# p8x-backplane-a.net
KiCad netlist of a schematic drawn in EAGLE
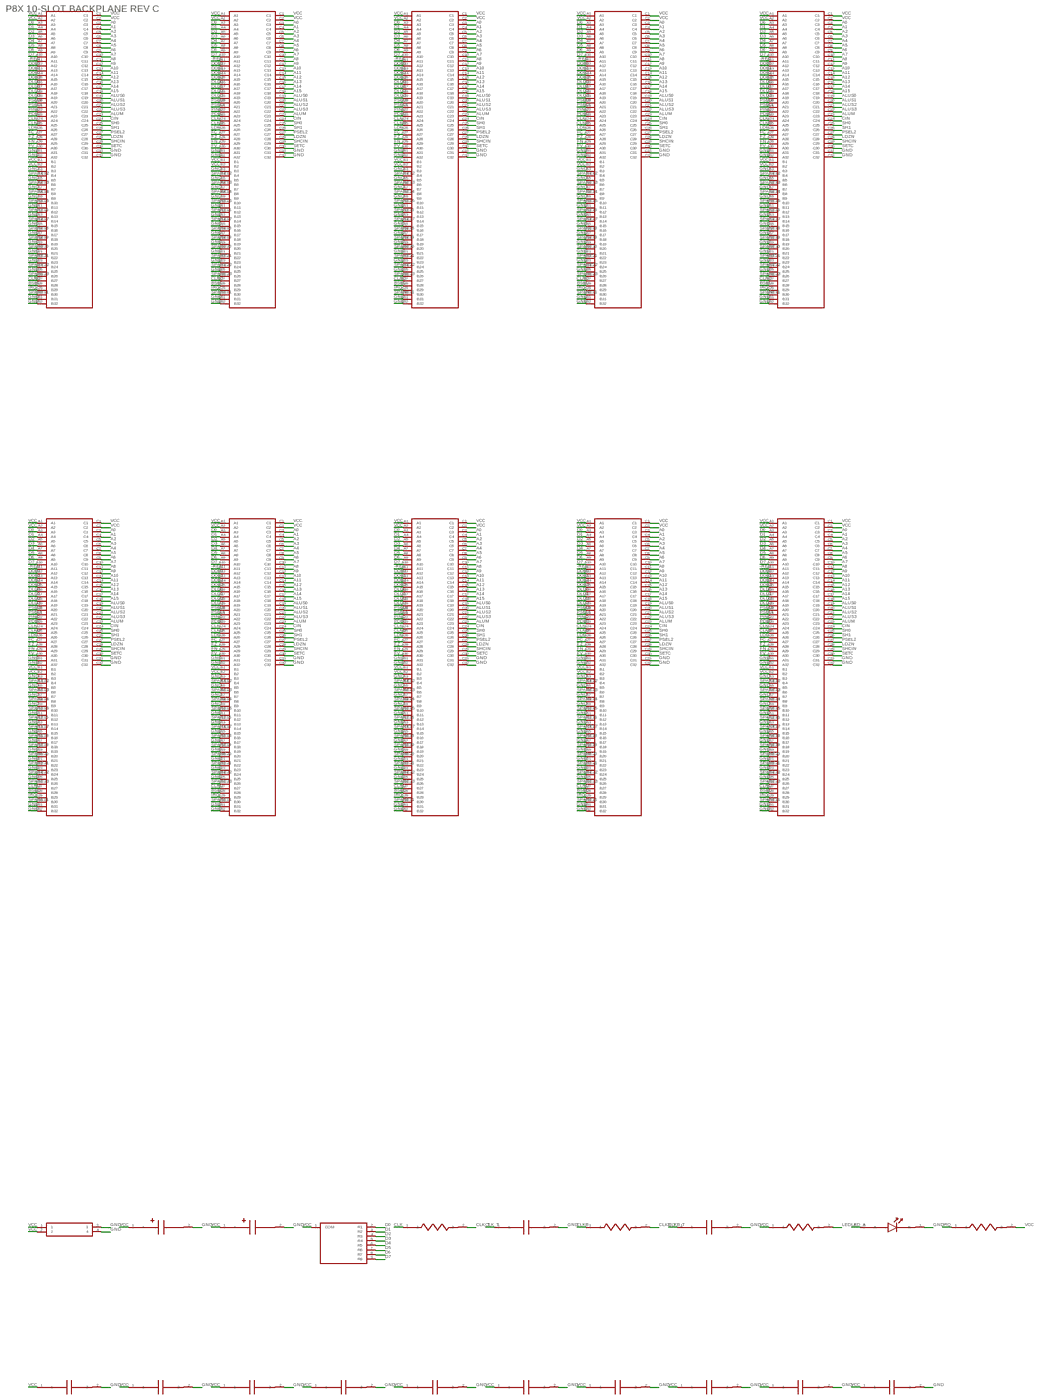
[diagram p0: schematic, sheet 1, overview]
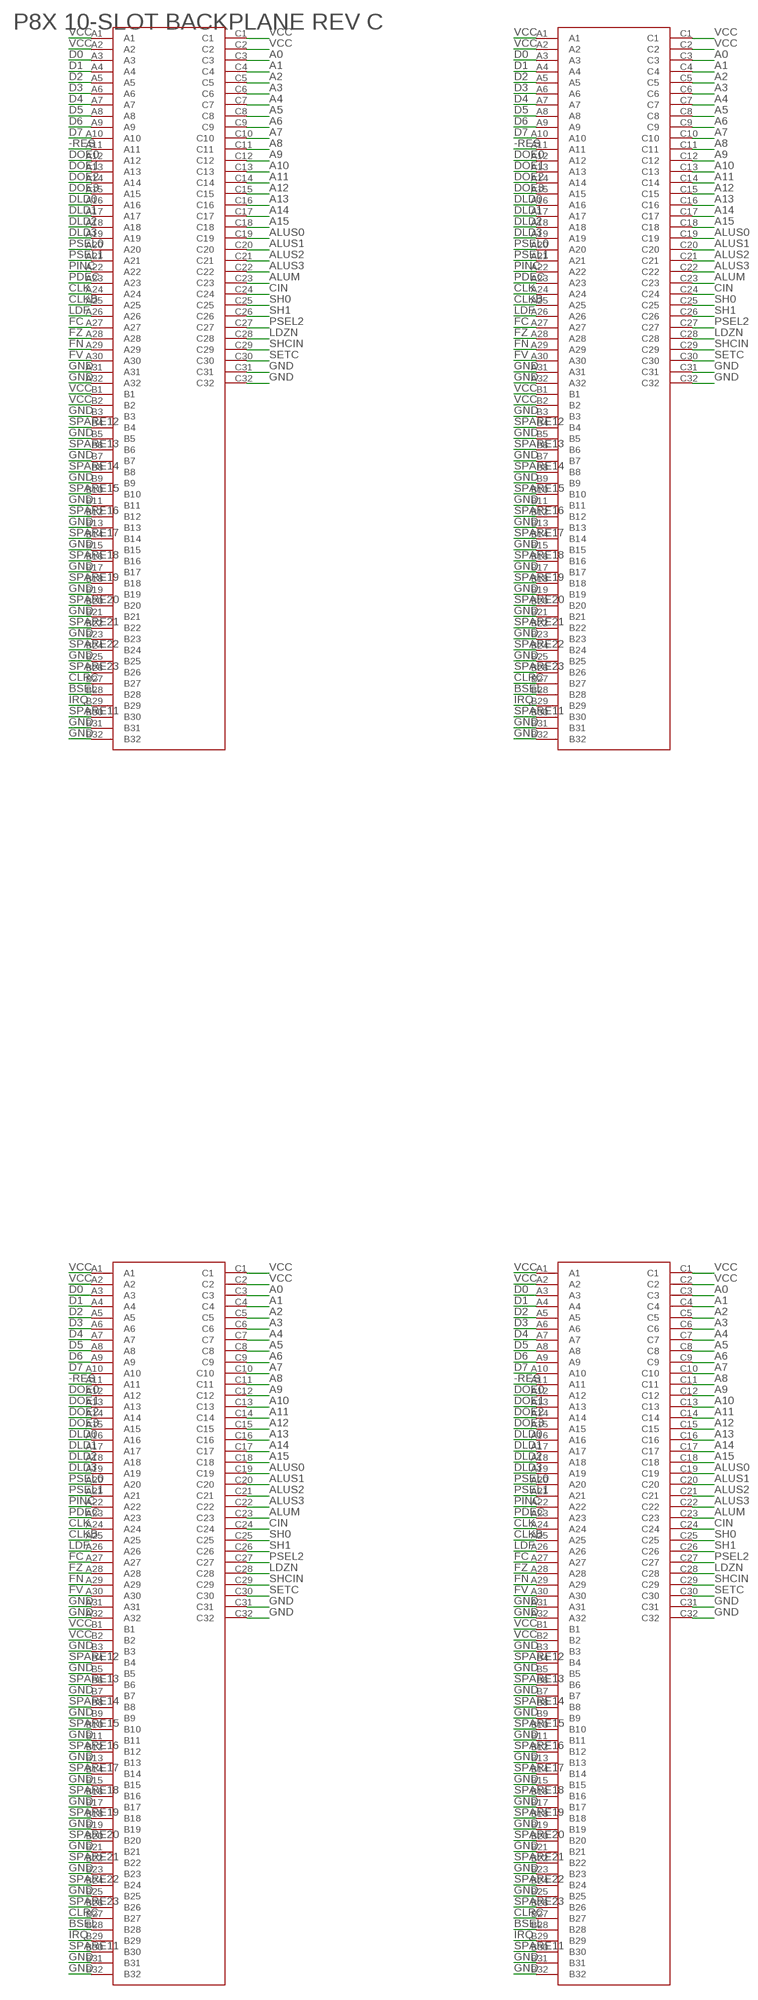
[diagram p1: schematic, sheet 1, part 1 of 4]
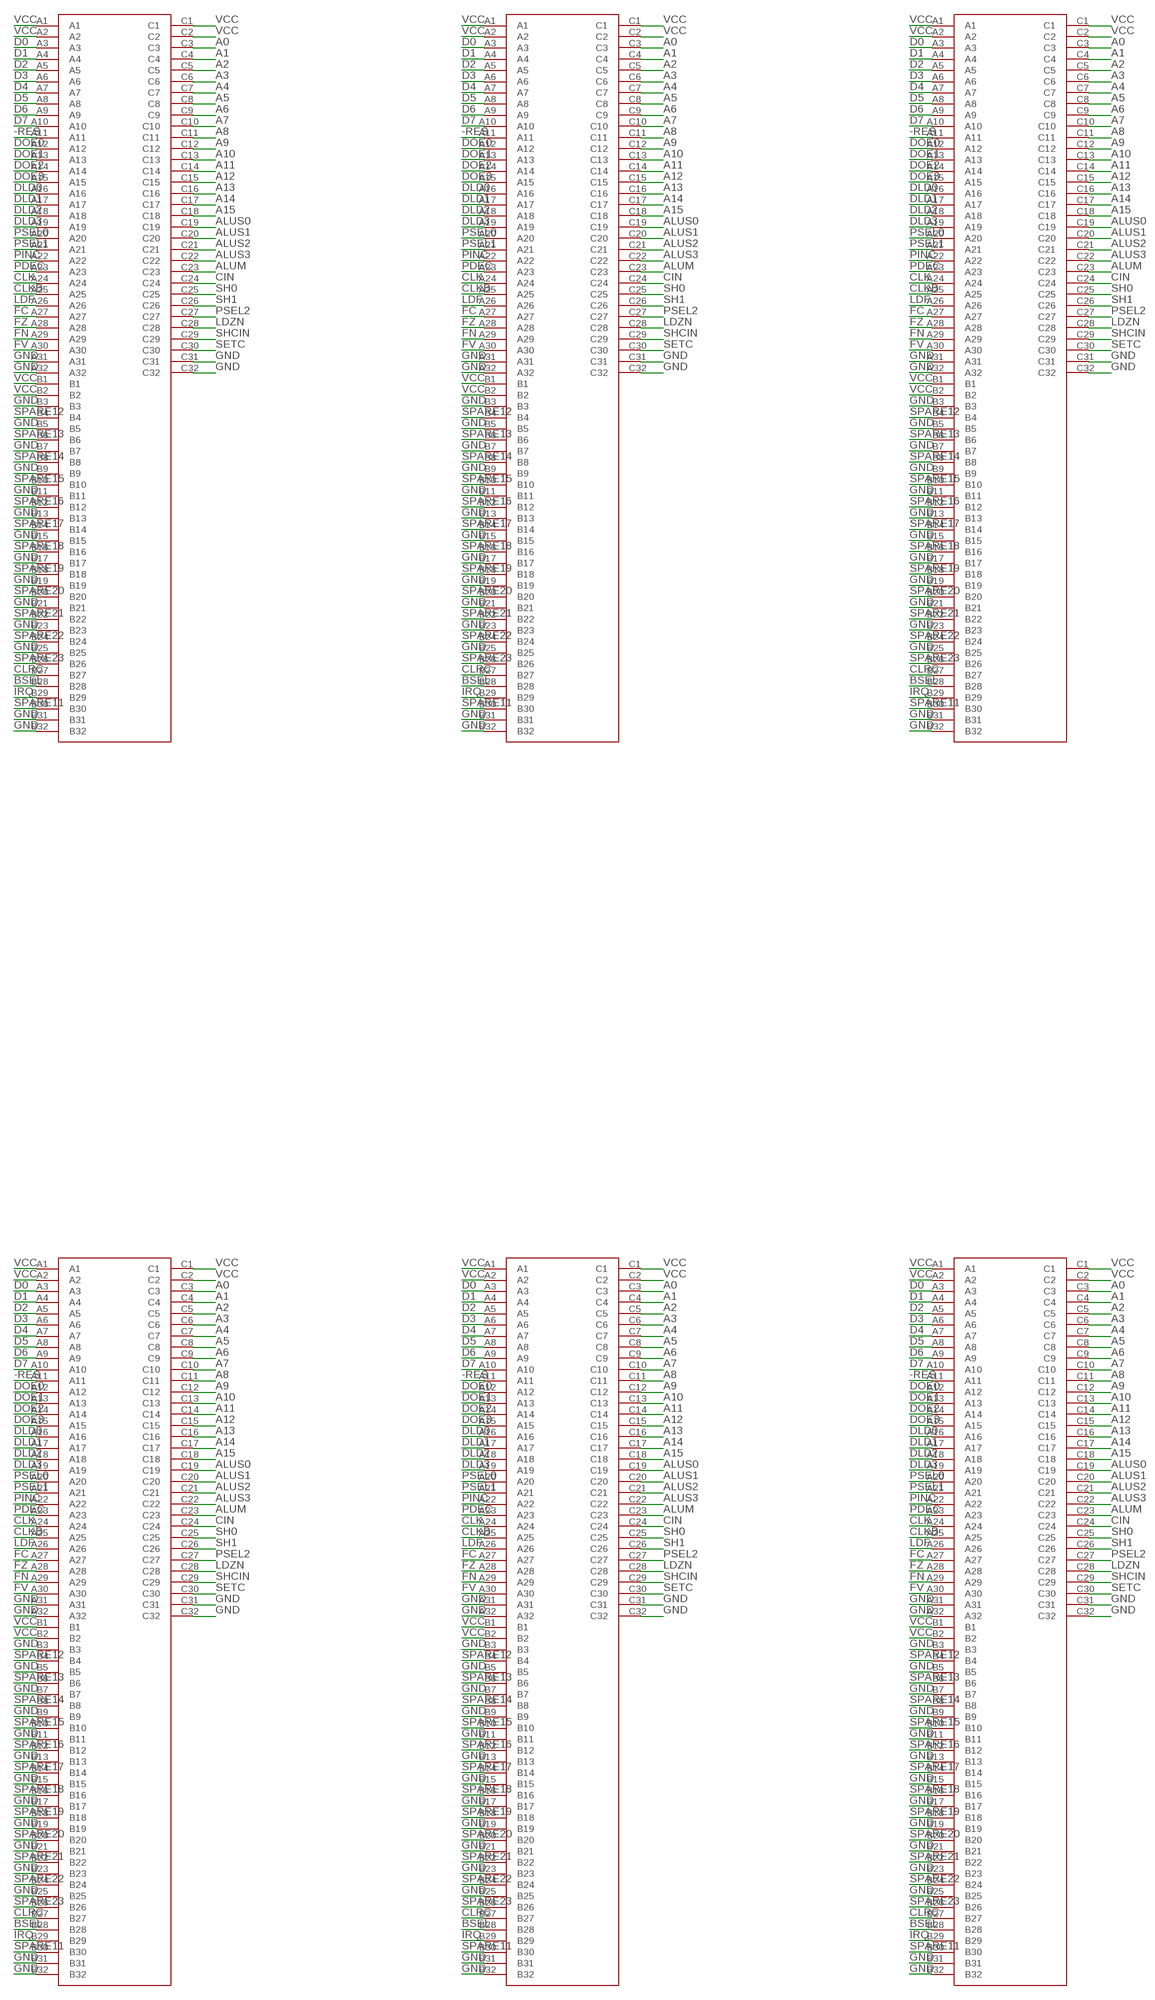
[diagram p2: schematic, sheet 1, part 2 of 4]
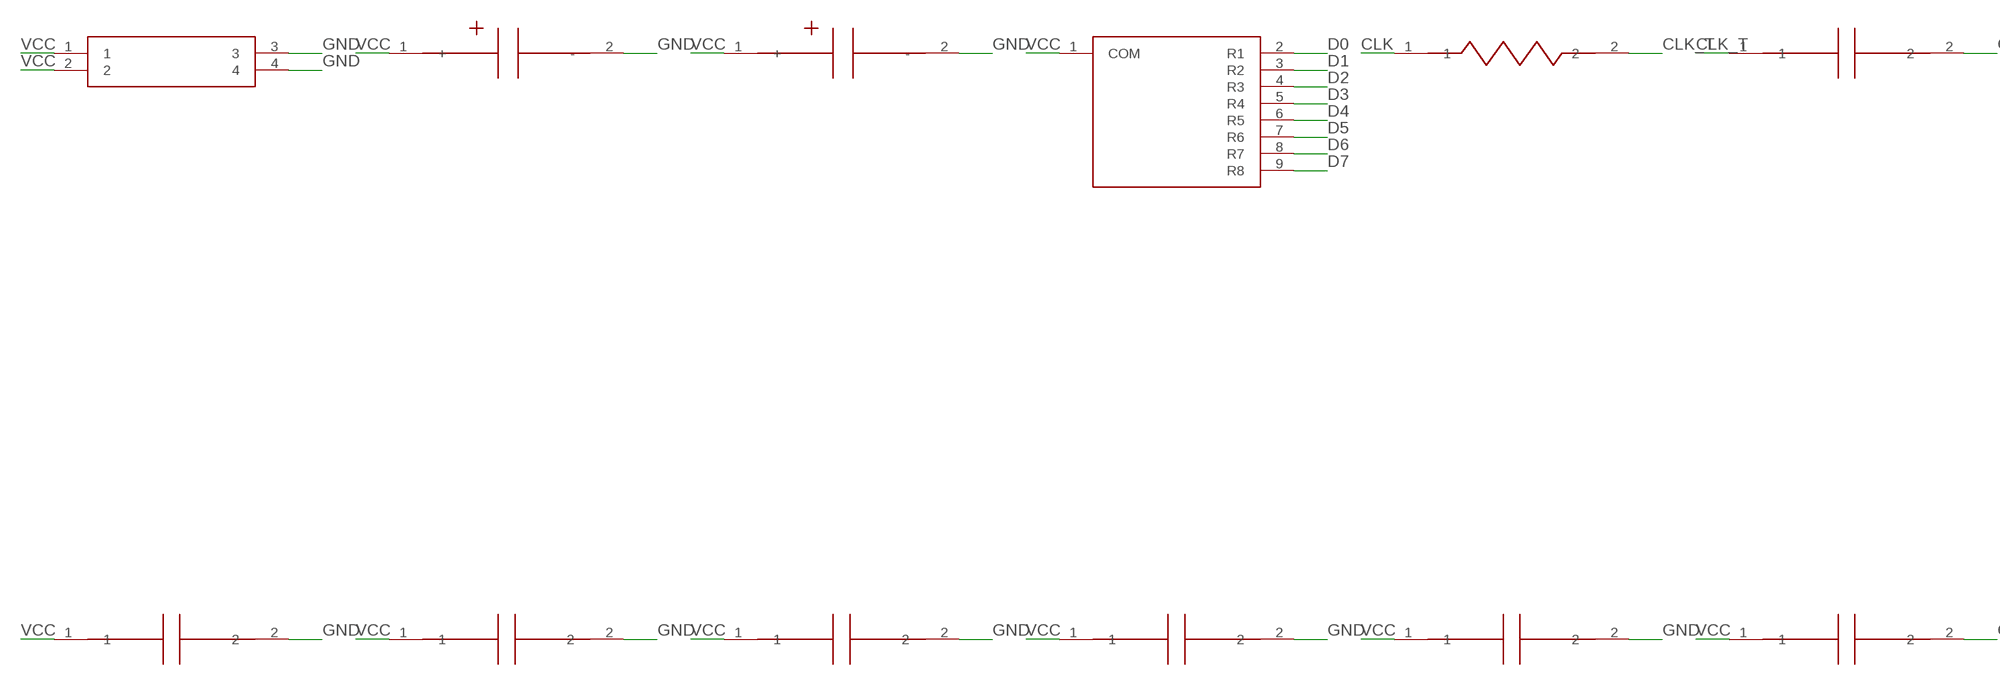
[diagram p3: schematic, sheet 1, part 3 of 4]
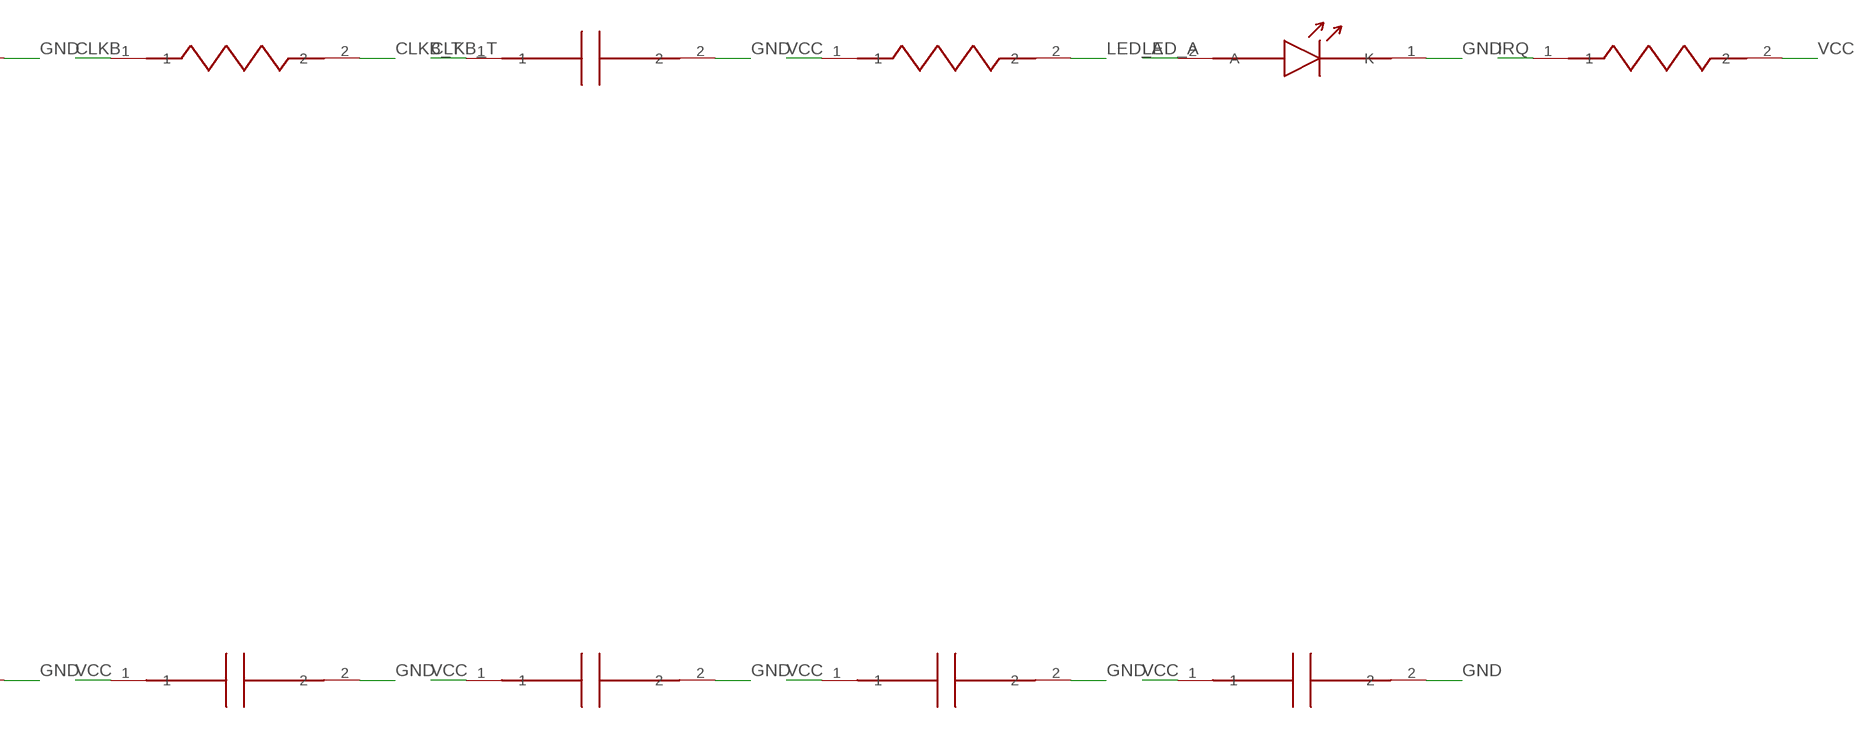
[diagram p4: schematic, sheet 1, part 4 of 4]

(export (version "E")
  (design (tool "Eeschema 10.0.6"))
  (components
    (comp (ref "C1")
      (value "100nF")
      (footprint "eagle-import:C_DISC1")
      (libsource (lib "eagle-import") (part "CAP1"))
    )
    (comp (ref "C2")
      (value "100nF")
      (footprint "eagle-import:C_DISC1")
      (libsource (lib "eagle-import") (part "CAP1"))
    )
    (comp (ref "C3")
      (value "100nF")
      (footprint "eagle-import:C_DISC1")
      (libsource (lib "eagle-import") (part "CAP1"))
    )
    (comp (ref "C4")
      (value "100nF")
      (footprint "eagle-import:C_DISC1")
      (libsource (lib "eagle-import") (part "CAP1"))
    )
    (comp (ref "C5")
      (value "100nF")
      (footprint "eagle-import:C_DISC1")
      (libsource (lib "eagle-import") (part "CAP1"))
    )
    (comp (ref "C6")
      (value "100nF")
      (footprint "eagle-import:C_DISC1")
      (libsource (lib "eagle-import") (part "CAP1"))
    )
    (comp (ref "C7")
      (value "100nF")
      (footprint "eagle-import:C_DISC1")
      (libsource (lib "eagle-import") (part "CAP1"))
    )
    (comp (ref "C8")
      (value "100nF")
      (footprint "eagle-import:C_DISC1")
      (libsource (lib "eagle-import") (part "CAP1"))
    )
    (comp (ref "C9")
      (value "100nF")
      (footprint "eagle-import:C_DISC1")
      (libsource (lib "eagle-import") (part "CAP1"))
    )
    (comp (ref "C10")
      (value "100nF")
      (footprint "eagle-import:C_DISC1")
      (libsource (lib "eagle-import") (part "CAP1"))
    )
    (comp (ref "C11")
      (value "470uF")
      (footprint "eagle-import:CP_RADIAL")
      (libsource (lib "eagle-import") (part "CAPP"))
    )
    (comp (ref "C12")
      (value "470uF")
      (footprint "eagle-import:CP_RADIAL")
      (libsource (lib "eagle-import") (part "CAPP"))
    )
    (comp (ref "C13")
      (value "150pF")
      (footprint "eagle-import:C_DISC")
      (libsource (lib "eagle-import") (part "CAP"))
    )
    (comp (ref "C14")
      (value "150pF")
      (footprint "eagle-import:C_DISC")
      (libsource (lib "eagle-import") (part "CAP"))
    )
    (comp (ref "J1")
      (value "SLOT1")
      (footprint "eagle-import:FABC96S")
      (libsource (lib "eagle-import") (part "DIN96"))
    )
    (comp (ref "J2")
      (value "SLOT2")
      (footprint "eagle-import:FABC96S")
      (libsource (lib "eagle-import") (part "DIN96"))
    )
    (comp (ref "J3")
      (value "SLOT3")
      (footprint "eagle-import:FABC96S")
      (libsource (lib "eagle-import") (part "DIN96"))
    )
    (comp (ref "J4")
      (value "SLOT4")
      (footprint "eagle-import:FABC96S")
      (libsource (lib "eagle-import") (part "DIN96"))
    )
    (comp (ref "J5")
      (value "SLOT5")
      (footprint "eagle-import:FABC96S")
      (libsource (lib "eagle-import") (part "DIN96"))
    )
    (comp (ref "J6")
      (value "SLOT6")
      (footprint "eagle-import:FABC96S")
      (libsource (lib "eagle-import") (part "DIN96"))
    )
    (comp (ref "J7")
      (value "SLOT7")
      (footprint "eagle-import:FABC96S")
      (libsource (lib "eagle-import") (part "DIN96"))
    )
    (comp (ref "J8")
      (value "SLOT8")
      (footprint "eagle-import:FABC96S")
      (libsource (lib "eagle-import") (part "DIN96"))
    )
    (comp (ref "J9")
      (value "SLOT9")
      (footprint "eagle-import:FABC96S")
      (libsource (lib "eagle-import") (part "DIN96"))
    )
    (comp (ref "J10")
      (value "SLOT10")
      (footprint "eagle-import:FABC96S")
      (libsource (lib "eagle-import") (part "DIN96"))
    )
    (comp (ref "J11")
      (value "PWR-5V")
      (footprint "eagle-import:TB4")
      (libsource (lib "eagle-import") (part "TB4"))
    )
    (comp (ref "LED1")
      (value "PWR")
      (footprint "eagle-import:LED5")
      (libsource (lib "eagle-import") (part "LED"))
    )
    (comp (ref "R1")
      (value "1K")
      (footprint "eagle-import:R_AXIAL")
      (libsource (lib "eagle-import") (part "RES"))
    )
    (comp (ref "R2")
      (value "100R")
      (footprint "eagle-import:R_AXIAL")
      (libsource (lib "eagle-import") (part "RES"))
    )
    (comp (ref "R3")
      (value "100R")
      (footprint "eagle-import:R_AXIAL")
      (libsource (lib "eagle-import") (part "RES"))
    )
    (comp (ref "R4")
      (value "10K")
      (footprint "eagle-import:R_AXIAL")
      (libsource (lib "eagle-import") (part "RES"))
    )
    (comp (ref "RN1")
      (value "8X10K")
      (footprint "eagle-import:SIP9")
      (libsource (lib "eagle-import") (part "SIP9"))
    )
  )
  (nets
    (net (code "1") (name "/-RES") (class "Default")
      (node (ref "J1") (pin "A11") (pinfunction "A11_A11") (pintype "bidirectional"))
      (node (ref "J10") (pin "A11") (pinfunction "A11_A11") (pintype "bidirectional"))
      (node (ref "J2") (pin "A11") (pinfunction "A11_A11") (pintype "bidirectional"))
      (node (ref "J3") (pin "A11") (pinfunction "A11_A11") (pintype "bidirectional"))
      (node (ref "J4") (pin "A11") (pinfunction "A11_A11") (pintype "bidirectional"))
      (node (ref "J5") (pin "A11") (pinfunction "A11_A11") (pintype "bidirectional"))
      (node (ref "J6") (pin "A11") (pinfunction "A11_A11") (pintype "bidirectional"))
      (node (ref "J7") (pin "A11") (pinfunction "A11_A11") (pintype "bidirectional"))
      (node (ref "J8") (pin "A11") (pinfunction "A11_A11") (pintype "bidirectional"))
      (node (ref "J9") (pin "A11") (pinfunction "A11_A11") (pintype "bidirectional"))
    )
    (net (code "2") (name "/A0") (class "Default")
      (node (ref "J1") (pin "C3") (pinfunction "C3_C3") (pintype "bidirectional"))
      (node (ref "J10") (pin "C3") (pinfunction "C3_C3") (pintype "bidirectional"))
      (node (ref "J2") (pin "C3") (pinfunction "C3_C3") (pintype "bidirectional"))
      (node (ref "J3") (pin "C3") (pinfunction "C3_C3") (pintype "bidirectional"))
      (node (ref "J4") (pin "C3") (pinfunction "C3_C3") (pintype "bidirectional"))
      (node (ref "J5") (pin "C3") (pinfunction "C3_C3") (pintype "bidirectional"))
      (node (ref "J6") (pin "C3") (pinfunction "C3_C3") (pintype "bidirectional"))
      (node (ref "J7") (pin "C3") (pinfunction "C3_C3") (pintype "bidirectional"))
      (node (ref "J8") (pin "C3") (pinfunction "C3_C3") (pintype "bidirectional"))
      (node (ref "J9") (pin "C3") (pinfunction "C3_C3") (pintype "bidirectional"))
    )
    (net (code "3") (name "/A1") (class "Default")
      (node (ref "J1") (pin "C4") (pinfunction "C4_C4") (pintype "bidirectional"))
      (node (ref "J10") (pin "C4") (pinfunction "C4_C4") (pintype "bidirectional"))
      (node (ref "J2") (pin "C4") (pinfunction "C4_C4") (pintype "bidirectional"))
      (node (ref "J3") (pin "C4") (pinfunction "C4_C4") (pintype "bidirectional"))
      (node (ref "J4") (pin "C4") (pinfunction "C4_C4") (pintype "bidirectional"))
      (node (ref "J5") (pin "C4") (pinfunction "C4_C4") (pintype "bidirectional"))
      (node (ref "J6") (pin "C4") (pinfunction "C4_C4") (pintype "bidirectional"))
      (node (ref "J7") (pin "C4") (pinfunction "C4_C4") (pintype "bidirectional"))
      (node (ref "J8") (pin "C4") (pinfunction "C4_C4") (pintype "bidirectional"))
      (node (ref "J9") (pin "C4") (pinfunction "C4_C4") (pintype "bidirectional"))
    )
    (net (code "4") (name "/A2") (class "Default")
      (node (ref "J1") (pin "C5") (pinfunction "C5_C5") (pintype "bidirectional"))
      (node (ref "J10") (pin "C5") (pinfunction "C5_C5") (pintype "bidirectional"))
      (node (ref "J2") (pin "C5") (pinfunction "C5_C5") (pintype "bidirectional"))
      (node (ref "J3") (pin "C5") (pinfunction "C5_C5") (pintype "bidirectional"))
      (node (ref "J4") (pin "C5") (pinfunction "C5_C5") (pintype "bidirectional"))
      (node (ref "J5") (pin "C5") (pinfunction "C5_C5") (pintype "bidirectional"))
      (node (ref "J6") (pin "C5") (pinfunction "C5_C5") (pintype "bidirectional"))
      (node (ref "J7") (pin "C5") (pinfunction "C5_C5") (pintype "bidirectional"))
      (node (ref "J8") (pin "C5") (pinfunction "C5_C5") (pintype "bidirectional"))
      (node (ref "J9") (pin "C5") (pinfunction "C5_C5") (pintype "bidirectional"))
    )
    (net (code "5") (name "/A3") (class "Default")
      (node (ref "J1") (pin "C6") (pinfunction "C6_C6") (pintype "bidirectional"))
      (node (ref "J10") (pin "C6") (pinfunction "C6_C6") (pintype "bidirectional"))
      (node (ref "J2") (pin "C6") (pinfunction "C6_C6") (pintype "bidirectional"))
      (node (ref "J3") (pin "C6") (pinfunction "C6_C6") (pintype "bidirectional"))
      (node (ref "J4") (pin "C6") (pinfunction "C6_C6") (pintype "bidirectional"))
      (node (ref "J5") (pin "C6") (pinfunction "C6_C6") (pintype "bidirectional"))
      (node (ref "J6") (pin "C6") (pinfunction "C6_C6") (pintype "bidirectional"))
      (node (ref "J7") (pin "C6") (pinfunction "C6_C6") (pintype "bidirectional"))
      (node (ref "J8") (pin "C6") (pinfunction "C6_C6") (pintype "bidirectional"))
      (node (ref "J9") (pin "C6") (pinfunction "C6_C6") (pintype "bidirectional"))
    )
    (net (code "6") (name "/A4") (class "Default")
      (node (ref "J1") (pin "C7") (pinfunction "C7_C7") (pintype "bidirectional"))
      (node (ref "J10") (pin "C7") (pinfunction "C7_C7") (pintype "bidirectional"))
      (node (ref "J2") (pin "C7") (pinfunction "C7_C7") (pintype "bidirectional"))
      (node (ref "J3") (pin "C7") (pinfunction "C7_C7") (pintype "bidirectional"))
      (node (ref "J4") (pin "C7") (pinfunction "C7_C7") (pintype "bidirectional"))
      (node (ref "J5") (pin "C7") (pinfunction "C7_C7") (pintype "bidirectional"))
      (node (ref "J6") (pin "C7") (pinfunction "C7_C7") (pintype "bidirectional"))
      (node (ref "J7") (pin "C7") (pinfunction "C7_C7") (pintype "bidirectional"))
      (node (ref "J8") (pin "C7") (pinfunction "C7_C7") (pintype "bidirectional"))
      (node (ref "J9") (pin "C7") (pinfunction "C7_C7") (pintype "bidirectional"))
    )
    (net (code "7") (name "/A5") (class "Default")
      (node (ref "J1") (pin "C8") (pinfunction "C8_C8") (pintype "bidirectional"))
      (node (ref "J10") (pin "C8") (pinfunction "C8_C8") (pintype "bidirectional"))
      (node (ref "J2") (pin "C8") (pinfunction "C8_C8") (pintype "bidirectional"))
      (node (ref "J3") (pin "C8") (pinfunction "C8_C8") (pintype "bidirectional"))
      (node (ref "J4") (pin "C8") (pinfunction "C8_C8") (pintype "bidirectional"))
      (node (ref "J5") (pin "C8") (pinfunction "C8_C8") (pintype "bidirectional"))
      (node (ref "J6") (pin "C8") (pinfunction "C8_C8") (pintype "bidirectional"))
      (node (ref "J7") (pin "C8") (pinfunction "C8_C8") (pintype "bidirectional"))
      (node (ref "J8") (pin "C8") (pinfunction "C8_C8") (pintype "bidirectional"))
      (node (ref "J9") (pin "C8") (pinfunction "C8_C8") (pintype "bidirectional"))
    )
    (net (code "8") (name "/A6") (class "Default")
      (node (ref "J1") (pin "C9") (pinfunction "C9_C9") (pintype "bidirectional"))
      (node (ref "J10") (pin "C9") (pinfunction "C9_C9") (pintype "bidirectional"))
      (node (ref "J2") (pin "C9") (pinfunction "C9_C9") (pintype "bidirectional"))
      (node (ref "J3") (pin "C9") (pinfunction "C9_C9") (pintype "bidirectional"))
      (node (ref "J4") (pin "C9") (pinfunction "C9_C9") (pintype "bidirectional"))
      (node (ref "J5") (pin "C9") (pinfunction "C9_C9") (pintype "bidirectional"))
      (node (ref "J6") (pin "C9") (pinfunction "C9_C9") (pintype "bidirectional"))
      (node (ref "J7") (pin "C9") (pinfunction "C9_C9") (pintype "bidirectional"))
      (node (ref "J8") (pin "C9") (pinfunction "C9_C9") (pintype "bidirectional"))
      (node (ref "J9") (pin "C9") (pinfunction "C9_C9") (pintype "bidirectional"))
    )
    (net (code "9") (name "/A7") (class "Default")
      (node (ref "J1") (pin "C10") (pinfunction "C10_C10") (pintype "bidirectional"))
      (node (ref "J10") (pin "C10") (pinfunction "C10_C10") (pintype "bidirectional"))
      (node (ref "J2") (pin "C10") (pinfunction "C10_C10") (pintype "bidirectional"))
      (node (ref "J3") (pin "C10") (pinfunction "C10_C10") (pintype "bidirectional"))
      (node (ref "J4") (pin "C10") (pinfunction "C10_C10") (pintype "bidirectional"))
      (node (ref "J5") (pin "C10") (pinfunction "C10_C10") (pintype "bidirectional"))
      (node (ref "J6") (pin "C10") (pinfunction "C10_C10") (pintype "bidirectional"))
      (node (ref "J7") (pin "C10") (pinfunction "C10_C10") (pintype "bidirectional"))
      (node (ref "J8") (pin "C10") (pinfunction "C10_C10") (pintype "bidirectional"))
      (node (ref "J9") (pin "C10") (pinfunction "C10_C10") (pintype "bidirectional"))
    )
    (net (code "10") (name "/A8") (class "Default")
      (node (ref "J1") (pin "C11") (pinfunction "C11_C11") (pintype "bidirectional"))
      (node (ref "J10") (pin "C11") (pinfunction "C11_C11") (pintype "bidirectional"))
      (node (ref "J2") (pin "C11") (pinfunction "C11_C11") (pintype "bidirectional"))
      (node (ref "J3") (pin "C11") (pinfunction "C11_C11") (pintype "bidirectional"))
      (node (ref "J4") (pin "C11") (pinfunction "C11_C11") (pintype "bidirectional"))
      (node (ref "J5") (pin "C11") (pinfunction "C11_C11") (pintype "bidirectional"))
      (node (ref "J6") (pin "C11") (pinfunction "C11_C11") (pintype "bidirectional"))
      (node (ref "J7") (pin "C11") (pinfunction "C11_C11") (pintype "bidirectional"))
      (node (ref "J8") (pin "C11") (pinfunction "C11_C11") (pintype "bidirectional"))
      (node (ref "J9") (pin "C11") (pinfunction "C11_C11") (pintype "bidirectional"))
    )
    (net (code "11") (name "/A9") (class "Default")
      (node (ref "J1") (pin "C12") (pinfunction "C12_C12") (pintype "bidirectional"))
      (node (ref "J10") (pin "C12") (pinfunction "C12_C12") (pintype "bidirectional"))
      (node (ref "J2") (pin "C12") (pinfunction "C12_C12") (pintype "bidirectional"))
      (node (ref "J3") (pin "C12") (pinfunction "C12_C12") (pintype "bidirectional"))
      (node (ref "J4") (pin "C12") (pinfunction "C12_C12") (pintype "bidirectional"))
      (node (ref "J5") (pin "C12") (pinfunction "C12_C12") (pintype "bidirectional"))
      (node (ref "J6") (pin "C12") (pinfunction "C12_C12") (pintype "bidirectional"))
      (node (ref "J7") (pin "C12") (pinfunction "C12_C12") (pintype "bidirectional"))
      (node (ref "J8") (pin "C12") (pinfunction "C12_C12") (pintype "bidirectional"))
      (node (ref "J9") (pin "C12") (pinfunction "C12_C12") (pintype "bidirectional"))
    )
    (net (code "12") (name "/A10") (class "Default")
      (node (ref "J1") (pin "C13") (pinfunction "C13_C13") (pintype "bidirectional"))
      (node (ref "J10") (pin "C13") (pinfunction "C13_C13") (pintype "bidirectional"))
      (node (ref "J2") (pin "C13") (pinfunction "C13_C13") (pintype "bidirectional"))
      (node (ref "J3") (pin "C13") (pinfunction "C13_C13") (pintype "bidirectional"))
      (node (ref "J4") (pin "C13") (pinfunction "C13_C13") (pintype "bidirectional"))
      (node (ref "J5") (pin "C13") (pinfunction "C13_C13") (pintype "bidirectional"))
      (node (ref "J6") (pin "C13") (pinfunction "C13_C13") (pintype "bidirectional"))
      (node (ref "J7") (pin "C13") (pinfunction "C13_C13") (pintype "bidirectional"))
      (node (ref "J8") (pin "C13") (pinfunction "C13_C13") (pintype "bidirectional"))
      (node (ref "J9") (pin "C13") (pinfunction "C13_C13") (pintype "bidirectional"))
    )
    (net (code "13") (name "/A11") (class "Default")
      (node (ref "J1") (pin "C14") (pinfunction "C14_C14") (pintype "bidirectional"))
      (node (ref "J10") (pin "C14") (pinfunction "C14_C14") (pintype "bidirectional"))
      (node (ref "J2") (pin "C14") (pinfunction "C14_C14") (pintype "bidirectional"))
      (node (ref "J3") (pin "C14") (pinfunction "C14_C14") (pintype "bidirectional"))
      (node (ref "J4") (pin "C14") (pinfunction "C14_C14") (pintype "bidirectional"))
      (node (ref "J5") (pin "C14") (pinfunction "C14_C14") (pintype "bidirectional"))
      (node (ref "J6") (pin "C14") (pinfunction "C14_C14") (pintype "bidirectional"))
      (node (ref "J7") (pin "C14") (pinfunction "C14_C14") (pintype "bidirectional"))
      (node (ref "J8") (pin "C14") (pinfunction "C14_C14") (pintype "bidirectional"))
      (node (ref "J9") (pin "C14") (pinfunction "C14_C14") (pintype "bidirectional"))
    )
    (net (code "14") (name "/A12") (class "Default")
      (node (ref "J1") (pin "C15") (pinfunction "C15_C15") (pintype "bidirectional"))
      (node (ref "J10") (pin "C15") (pinfunction "C15_C15") (pintype "bidirectional"))
      (node (ref "J2") (pin "C15") (pinfunction "C15_C15") (pintype "bidirectional"))
      (node (ref "J3") (pin "C15") (pinfunction "C15_C15") (pintype "bidirectional"))
      (node (ref "J4") (pin "C15") (pinfunction "C15_C15") (pintype "bidirectional"))
      (node (ref "J5") (pin "C15") (pinfunction "C15_C15") (pintype "bidirectional"))
      (node (ref "J6") (pin "C15") (pinfunction "C15_C15") (pintype "bidirectional"))
      (node (ref "J7") (pin "C15") (pinfunction "C15_C15") (pintype "bidirectional"))
      (node (ref "J8") (pin "C15") (pinfunction "C15_C15") (pintype "bidirectional"))
      (node (ref "J9") (pin "C15") (pinfunction "C15_C15") (pintype "bidirectional"))
    )
    (net (code "15") (name "/A13") (class "Default")
      (node (ref "J1") (pin "C16") (pinfunction "C16_C16") (pintype "bidirectional"))
      (node (ref "J10") (pin "C16") (pinfunction "C16_C16") (pintype "bidirectional"))
      (node (ref "J2") (pin "C16") (pinfunction "C16_C16") (pintype "bidirectional"))
      (node (ref "J3") (pin "C16") (pinfunction "C16_C16") (pintype "bidirectional"))
      (node (ref "J4") (pin "C16") (pinfunction "C16_C16") (pintype "bidirectional"))
      (node (ref "J5") (pin "C16") (pinfunction "C16_C16") (pintype "bidirectional"))
      (node (ref "J6") (pin "C16") (pinfunction "C16_C16") (pintype "bidirectional"))
      (node (ref "J7") (pin "C16") (pinfunction "C16_C16") (pintype "bidirectional"))
      (node (ref "J8") (pin "C16") (pinfunction "C16_C16") (pintype "bidirectional"))
      (node (ref "J9") (pin "C16") (pinfunction "C16_C16") (pintype "bidirectional"))
    )
    (net (code "16") (name "/A14") (class "Default")
      (node (ref "J1") (pin "C17") (pinfunction "C17_C17") (pintype "bidirectional"))
      (node (ref "J10") (pin "C17") (pinfunction "C17_C17") (pintype "bidirectional"))
      (node (ref "J2") (pin "C17") (pinfunction "C17_C17") (pintype "bidirectional"))
      (node (ref "J3") (pin "C17") (pinfunction "C17_C17") (pintype "bidirectional"))
      (node (ref "J4") (pin "C17") (pinfunction "C17_C17") (pintype "bidirectional"))
      (node (ref "J5") (pin "C17") (pinfunction "C17_C17") (pintype "bidirectional"))
      (node (ref "J6") (pin "C17") (pinfunction "C17_C17") (pintype "bidirectional"))
      (node (ref "J7") (pin "C17") (pinfunction "C17_C17") (pintype "bidirectional"))
      (node (ref "J8") (pin "C17") (pinfunction "C17_C17") (pintype "bidirectional"))
      (node (ref "J9") (pin "C17") (pinfunction "C17_C17") (pintype "bidirectional"))
    )
    (net (code "17") (name "/A15") (class "Default")
      (node (ref "J1") (pin "C18") (pinfunction "C18_C18") (pintype "bidirectional"))
      (node (ref "J10") (pin "C18") (pinfunction "C18_C18") (pintype "bidirectional"))
      (node (ref "J2") (pin "C18") (pinfunction "C18_C18") (pintype "bidirectional"))
      (node (ref "J3") (pin "C18") (pinfunction "C18_C18") (pintype "bidirectional"))
      (node (ref "J4") (pin "C18") (pinfunction "C18_C18") (pintype "bidirectional"))
      (node (ref "J5") (pin "C18") (pinfunction "C18_C18") (pintype "bidirectional"))
      (node (ref "J6") (pin "C18") (pinfunction "C18_C18") (pintype "bidirectional"))
      (node (ref "J7") (pin "C18") (pinfunction "C18_C18") (pintype "bidirectional"))
      (node (ref "J8") (pin "C18") (pinfunction "C18_C18") (pintype "bidirectional"))
      (node (ref "J9") (pin "C18") (pinfunction "C18_C18") (pintype "bidirectional"))
    )
    (net (code "18") (name "/ALUM") (class "Default")
      (node (ref "J1") (pin "C23") (pinfunction "C23_C23") (pintype "bidirectional"))
      (node (ref "J10") (pin "C23") (pinfunction "C23_C23") (pintype "bidirectional"))
      (node (ref "J2") (pin "C23") (pinfunction "C23_C23") (pintype "bidirectional"))
      (node (ref "J3") (pin "C23") (pinfunction "C23_C23") (pintype "bidirectional"))
      (node (ref "J4") (pin "C23") (pinfunction "C23_C23") (pintype "bidirectional"))
      (node (ref "J5") (pin "C23") (pinfunction "C23_C23") (pintype "bidirectional"))
      (node (ref "J6") (pin "C23") (pinfunction "C23_C23") (pintype "bidirectional"))
      (node (ref "J7") (pin "C23") (pinfunction "C23_C23") (pintype "bidirectional"))
      (node (ref "J8") (pin "C23") (pinfunction "C23_C23") (pintype "bidirectional"))
      (node (ref "J9") (pin "C23") (pinfunction "C23_C23") (pintype "bidirectional"))
    )
    (net (code "19") (name "/ALUS0") (class "Default")
      (node (ref "J1") (pin "C19") (pinfunction "C19_C19") (pintype "bidirectional"))
      (node (ref "J10") (pin "C19") (pinfunction "C19_C19") (pintype "bidirectional"))
      (node (ref "J2") (pin "C19") (pinfunction "C19_C19") (pintype "bidirectional"))
      (node (ref "J3") (pin "C19") (pinfunction "C19_C19") (pintype "bidirectional"))
      (node (ref "J4") (pin "C19") (pinfunction "C19_C19") (pintype "bidirectional"))
      (node (ref "J5") (pin "C19") (pinfunction "C19_C19") (pintype "bidirectional"))
      (node (ref "J6") (pin "C19") (pinfunction "C19_C19") (pintype "bidirectional"))
      (node (ref "J7") (pin "C19") (pinfunction "C19_C19") (pintype "bidirectional"))
      (node (ref "J8") (pin "C19") (pinfunction "C19_C19") (pintype "bidirectional"))
      (node (ref "J9") (pin "C19") (pinfunction "C19_C19") (pintype "bidirectional"))
    )
    (net (code "20") (name "/ALUS1") (class "Default")
      (node (ref "J1") (pin "C20") (pinfunction "C20_C20") (pintype "bidirectional"))
      (node (ref "J10") (pin "C20") (pinfunction "C20_C20") (pintype "bidirectional"))
      (node (ref "J2") (pin "C20") (pinfunction "C20_C20") (pintype "bidirectional"))
      (node (ref "J3") (pin "C20") (pinfunction "C20_C20") (pintype "bidirectional"))
      (node (ref "J4") (pin "C20") (pinfunction "C20_C20") (pintype "bidirectional"))
      (node (ref "J5") (pin "C20") (pinfunction "C20_C20") (pintype "bidirectional"))
      (node (ref "J6") (pin "C20") (pinfunction "C20_C20") (pintype "bidirectional"))
      (node (ref "J7") (pin "C20") (pinfunction "C20_C20") (pintype "bidirectional"))
      (node (ref "J8") (pin "C20") (pinfunction "C20_C20") (pintype "bidirectional"))
      (node (ref "J9") (pin "C20") (pinfunction "C20_C20") (pintype "bidirectional"))
    )
    (net (code "21") (name "/ALUS2") (class "Default")
      (node (ref "J1") (pin "C21") (pinfunction "C21_C21") (pintype "bidirectional"))
      (node (ref "J10") (pin "C21") (pinfunction "C21_C21") (pintype "bidirectional"))
      (node (ref "J2") (pin "C21") (pinfunction "C21_C21") (pintype "bidirectional"))
      (node (ref "J3") (pin "C21") (pinfunction "C21_C21") (pintype "bidirectional"))
      (node (ref "J4") (pin "C21") (pinfunction "C21_C21") (pintype "bidirectional"))
      (node (ref "J5") (pin "C21") (pinfunction "C21_C21") (pintype "bidirectional"))
      (node (ref "J6") (pin "C21") (pinfunction "C21_C21") (pintype "bidirectional"))
      (node (ref "J7") (pin "C21") (pinfunction "C21_C21") (pintype "bidirectional"))
      (node (ref "J8") (pin "C21") (pinfunction "C21_C21") (pintype "bidirectional"))
      (node (ref "J9") (pin "C21") (pinfunction "C21_C21") (pintype "bidirectional"))
    )
    (net (code "22") (name "/ALUS3") (class "Default")
      (node (ref "J1") (pin "C22") (pinfunction "C22_C22") (pintype "bidirectional"))
      (node (ref "J10") (pin "C22") (pinfunction "C22_C22") (pintype "bidirectional"))
      (node (ref "J2") (pin "C22") (pinfunction "C22_C22") (pintype "bidirectional"))
      (node (ref "J3") (pin "C22") (pinfunction "C22_C22") (pintype "bidirectional"))
      (node (ref "J4") (pin "C22") (pinfunction "C22_C22") (pintype "bidirectional"))
      (node (ref "J5") (pin "C22") (pinfunction "C22_C22") (pintype "bidirectional"))
      (node (ref "J6") (pin "C22") (pinfunction "C22_C22") (pintype "bidirectional"))
      (node (ref "J7") (pin "C22") (pinfunction "C22_C22") (pintype "bidirectional"))
      (node (ref "J8") (pin "C22") (pinfunction "C22_C22") (pintype "bidirectional"))
      (node (ref "J9") (pin "C22") (pinfunction "C22_C22") (pintype "bidirectional"))
    )
    (net (code "23") (name "/BSEL") (class "Default")
      (node (ref "J1") (pin "B28") (pinfunction "B28_B28") (pintype "bidirectional"))
      (node (ref "J10") (pin "B28") (pinfunction "B28_B28") (pintype "bidirectional"))
      (node (ref "J2") (pin "B28") (pinfunction "B28_B28") (pintype "bidirectional"))
      (node (ref "J3") (pin "B28") (pinfunction "B28_B28") (pintype "bidirectional"))
      (node (ref "J4") (pin "B28") (pinfunction "B28_B28") (pintype "bidirectional"))
      (node (ref "J5") (pin "B28") (pinfunction "B28_B28") (pintype "bidirectional"))
      (node (ref "J6") (pin "B28") (pinfunction "B28_B28") (pintype "bidirectional"))
      (node (ref "J7") (pin "B28") (pinfunction "B28_B28") (pintype "bidirectional"))
      (node (ref "J8") (pin "B28") (pinfunction "B28_B28") (pintype "bidirectional"))
      (node (ref "J9") (pin "B28") (pinfunction "B28_B28") (pintype "bidirectional"))
    )
    (net (code "24") (name "/CIN") (class "Default")
      (node (ref "J1") (pin "C24") (pinfunction "C24_C24") (pintype "bidirectional"))
      (node (ref "J10") (pin "C24") (pinfunction "C24_C24") (pintype "bidirectional"))
      (node (ref "J2") (pin "C24") (pinfunction "C24_C24") (pintype "bidirectional"))
      (node (ref "J3") (pin "C24") (pinfunction "C24_C24") (pintype "bidirectional"))
      (node (ref "J4") (pin "C24") (pinfunction "C24_C24") (pintype "bidirectional"))
      (node (ref "J5") (pin "C24") (pinfunction "C24_C24") (pintype "bidirectional"))
      (node (ref "J6") (pin "C24") (pinfunction "C24_C24") (pintype "bidirectional"))
      (node (ref "J7") (pin "C24") (pinfunction "C24_C24") (pintype "bidirectional"))
      (node (ref "J8") (pin "C24") (pinfunction "C24_C24") (pintype "bidirectional"))
      (node (ref "J9") (pin "C24") (pinfunction "C24_C24") (pintype "bidirectional"))
    )
    (net (code "25") (name "/CLK") (class "Default")
      (node (ref "J1") (pin "A24") (pinfunction "A24_A24") (pintype "bidirectional"))
      (node (ref "J10") (pin "A24") (pinfunction "A24_A24") (pintype "bidirectional"))
      (node (ref "J2") (pin "A24") (pinfunction "A24_A24") (pintype "bidirectional"))
      (node (ref "J3") (pin "A24") (pinfunction "A24_A24") (pintype "bidirectional"))
      (node (ref "J4") (pin "A24") (pinfunction "A24_A24") (pintype "bidirectional"))
      (node (ref "J5") (pin "A24") (pinfunction "A24_A24") (pintype "bidirectional"))
      (node (ref "J6") (pin "A24") (pinfunction "A24_A24") (pintype "bidirectional"))
      (node (ref "J7") (pin "A24") (pinfunction "A24_A24") (pintype "bidirectional"))
      (node (ref "J8") (pin "A24") (pinfunction "A24_A24") (pintype "bidirectional"))
      (node (ref "J9") (pin "A24") (pinfunction "A24_A24") (pintype "bidirectional"))
      (node (ref "R2") (pin "1") (pinfunction "1_1") (pintype "bidirectional"))
    )
    (net (code "26") (name "/CLKB") (class "Default")
      (node (ref "J1") (pin "A25") (pinfunction "A25_A25") (pintype "bidirectional"))
      (node (ref "J10") (pin "A25") (pinfunction "A25_A25") (pintype "bidirectional"))
      (node (ref "J2") (pin "A25") (pinfunction "A25_A25") (pintype "bidirectional"))
      (node (ref "J3") (pin "A25") (pinfunction "A25_A25") (pintype "bidirectional"))
      (node (ref "J4") (pin "A25") (pinfunction "A25_A25") (pintype "bidirectional"))
      (node (ref "J5") (pin "A25") (pinfunction "A25_A25") (pintype "bidirectional"))
      (node (ref "J6") (pin "A25") (pinfunction "A25_A25") (pintype "bidirectional"))
      (node (ref "J7") (pin "A25") (pinfunction "A25_A25") (pintype "bidirectional"))
      (node (ref "J8") (pin "A25") (pinfunction "A25_A25") (pintype "bidirectional"))
      (node (ref "J9") (pin "A25") (pinfunction "A25_A25") (pintype "bidirectional"))
      (node (ref "R3") (pin "1") (pinfunction "1_1") (pintype "bidirectional"))
    )
    (net (code "27") (name "/CLKB_T") (class "Default")
      (node (ref "C14") (pin "1") (pinfunction "1_1") (pintype "bidirectional"))
      (node (ref "R3") (pin "2") (pinfunction "2_2") (pintype "bidirectional"))
    )
    (net (code "28") (name "/CLK_T") (class "Default")
      (node (ref "C13") (pin "1") (pinfunction "1_1") (pintype "bidirectional"))
      (node (ref "R2") (pin "2") (pinfunction "2_2") (pintype "bidirectional"))
    )
    (net (code "29") (name "/CLRC") (class "Default")
      (node (ref "J1") (pin "B27") (pinfunction "B27_B27") (pintype "bidirectional"))
      (node (ref "J10") (pin "B27") (pinfunction "B27_B27") (pintype "bidirectional"))
      (node (ref "J2") (pin "B27") (pinfunction "B27_B27") (pintype "bidirectional"))
      (node (ref "J3") (pin "B27") (pinfunction "B27_B27") (pintype "bidirectional"))
      (node (ref "J4") (pin "B27") (pinfunction "B27_B27") (pintype "bidirectional"))
      (node (ref "J5") (pin "B27") (pinfunction "B27_B27") (pintype "bidirectional"))
      (node (ref "J6") (pin "B27") (pinfunction "B27_B27") (pintype "bidirectional"))
      (node (ref "J7") (pin "B27") (pinfunction "B27_B27") (pintype "bidirectional"))
      (node (ref "J8") (pin "B27") (pinfunction "B27_B27") (pintype "bidirectional"))
      (node (ref "J9") (pin "B27") (pinfunction "B27_B27") (pintype "bidirectional"))
    )
    (net (code "30") (name "/D0") (class "Default")
      (node (ref "J1") (pin "A3") (pinfunction "A3_A3") (pintype "bidirectional"))
      (node (ref "J10") (pin "A3") (pinfunction "A3_A3") (pintype "bidirectional"))
      (node (ref "J2") (pin "A3") (pinfunction "A3_A3") (pintype "bidirectional"))
      (node (ref "J3") (pin "A3") (pinfunction "A3_A3") (pintype "bidirectional"))
      (node (ref "J4") (pin "A3") (pinfunction "A3_A3") (pintype "bidirectional"))
      (node (ref "J5") (pin "A3") (pinfunction "A3_A3") (pintype "bidirectional"))
      (node (ref "J6") (pin "A3") (pinfunction "A3_A3") (pintype "bidirectional"))
      (node (ref "J7") (pin "A3") (pinfunction "A3_A3") (pintype "bidirectional"))
      (node (ref "J8") (pin "A3") (pinfunction "A3_A3") (pintype "bidirectional"))
      (node (ref "J9") (pin "A3") (pinfunction "A3_A3") (pintype "bidirectional"))
      (node (ref "RN1") (pin "2") (pinfunction "R1_2") (pintype "bidirectional"))
    )
    (net (code "31") (name "/D1") (class "Default")
      (node (ref "J1") (pin "A4") (pinfunction "A4_A4") (pintype "bidirectional"))
      (node (ref "J10") (pin "A4") (pinfunction "A4_A4") (pintype "bidirectional"))
      (node (ref "J2") (pin "A4") (pinfunction "A4_A4") (pintype "bidirectional"))
      (node (ref "J3") (pin "A4") (pinfunction "A4_A4") (pintype "bidirectional"))
      (node (ref "J4") (pin "A4") (pinfunction "A4_A4") (pintype "bidirectional"))
      (node (ref "J5") (pin "A4") (pinfunction "A4_A4") (pintype "bidirectional"))
      (node (ref "J6") (pin "A4") (pinfunction "A4_A4") (pintype "bidirectional"))
      (node (ref "J7") (pin "A4") (pinfunction "A4_A4") (pintype "bidirectional"))
      (node (ref "J8") (pin "A4") (pinfunction "A4_A4") (pintype "bidirectional"))
      (node (ref "J9") (pin "A4") (pinfunction "A4_A4") (pintype "bidirectional"))
      (node (ref "RN1") (pin "3") (pinfunction "R2_3") (pintype "bidirectional"))
    )
    (net (code "32") (name "/D2") (class "Default")
      (node (ref "J1") (pin "A5") (pinfunction "A5_A5") (pintype "bidirectional"))
      (node (ref "J10") (pin "A5") (pinfunction "A5_A5") (pintype "bidirectional"))
      (node (ref "J2") (pin "A5") (pinfunction "A5_A5") (pintype "bidirectional"))
      (node (ref "J3") (pin "A5") (pinfunction "A5_A5") (pintype "bidirectional"))
      (node (ref "J4") (pin "A5") (pinfunction "A5_A5") (pintype "bidirectional"))
      (node (ref "J5") (pin "A5") (pinfunction "A5_A5") (pintype "bidirectional"))
      (node (ref "J6") (pin "A5") (pinfunction "A5_A5") (pintype "bidirectional"))
      (node (ref "J7") (pin "A5") (pinfunction "A5_A5") (pintype "bidirectional"))
      (node (ref "J8") (pin "A5") (pinfunction "A5_A5") (pintype "bidirectional"))
      (node (ref "J9") (pin "A5") (pinfunction "A5_A5") (pintype "bidirectional"))
      (node (ref "RN1") (pin "4") (pinfunction "R3_4") (pintype "bidirectional"))
    )
    (net (code "33") (name "/D3") (class "Default")
      (node (ref "J1") (pin "A6") (pinfunction "A6_A6") (pintype "bidirectional"))
      (node (ref "J10") (pin "A6") (pinfunction "A6_A6") (pintype "bidirectional"))
      (node (ref "J2") (pin "A6") (pinfunction "A6_A6") (pintype "bidirectional"))
      (node (ref "J3") (pin "A6") (pinfunction "A6_A6") (pintype "bidirectional"))
      (node (ref "J4") (pin "A6") (pinfunction "A6_A6") (pintype "bidirectional"))
      (node (ref "J5") (pin "A6") (pinfunction "A6_A6") (pintype "bidirectional"))
      (node (ref "J6") (pin "A6") (pinfunction "A6_A6") (pintype "bidirectional"))
      (node (ref "J7") (pin "A6") (pinfunction "A6_A6") (pintype "bidirectional"))
      (node (ref "J8") (pin "A6") (pinfunction "A6_A6") (pintype "bidirectional"))
      (node (ref "J9") (pin "A6") (pinfunction "A6_A6") (pintype "bidirectional"))
      (node (ref "RN1") (pin "5") (pinfunction "R4_5") (pintype "bidirectional"))
    )
    (net (code "34") (name "/D4") (class "Default")
      (node (ref "J1") (pin "A7") (pinfunction "A7_A7") (pintype "bidirectional"))
      (node (ref "J10") (pin "A7") (pinfunction "A7_A7") (pintype "bidirectional"))
      (node (ref "J2") (pin "A7") (pinfunction "A7_A7") (pintype "bidirectional"))
      (node (ref "J3") (pin "A7") (pinfunction "A7_A7") (pintype "bidirectional"))
      (node (ref "J4") (pin "A7") (pinfunction "A7_A7") (pintype "bidirectional"))
      (node (ref "J5") (pin "A7") (pinfunction "A7_A7") (pintype "bidirectional"))
      (node (ref "J6") (pin "A7") (pinfunction "A7_A7") (pintype "bidirectional"))
      (node (ref "J7") (pin "A7") (pinfunction "A7_A7") (pintype "bidirectional"))
      (node (ref "J8") (pin "A7") (pinfunction "A7_A7") (pintype "bidirectional"))
      (node (ref "J9") (pin "A7") (pinfunction "A7_A7") (pintype "bidirectional"))
      (node (ref "RN1") (pin "6") (pinfunction "R5_6") (pintype "bidirectional"))
    )
    (net (code "35") (name "/D5") (class "Default")
      (node (ref "J1") (pin "A8") (pinfunction "A8_A8") (pintype "bidirectional"))
      (node (ref "J10") (pin "A8") (pinfunction "A8_A8") (pintype "bidirectional"))
      (node (ref "J2") (pin "A8") (pinfunction "A8_A8") (pintype "bidirectional"))
      (node (ref "J3") (pin "A8") (pinfunction "A8_A8") (pintype "bidirectional"))
      (node (ref "J4") (pin "A8") (pinfunction "A8_A8") (pintype "bidirectional"))
      (node (ref "J5") (pin "A8") (pinfunction "A8_A8") (pintype "bidirectional"))
      (node (ref "J6") (pin "A8") (pinfunction "A8_A8") (pintype "bidirectional"))
      (node (ref "J7") (pin "A8") (pinfunction "A8_A8") (pintype "bidirectional"))
      (node (ref "J8") (pin "A8") (pinfunction "A8_A8") (pintype "bidirectional"))
      (node (ref "J9") (pin "A8") (pinfunction "A8_A8") (pintype "bidirectional"))
      (node (ref "RN1") (pin "7") (pinfunction "R6_7") (pintype "bidirectional"))
    )
    (net (code "36") (name "/D6") (class "Default")
      (node (ref "J1") (pin "A9") (pinfunction "A9_A9") (pintype "bidirectional"))
      (node (ref "J10") (pin "A9") (pinfunction "A9_A9") (pintype "bidirectional"))
      (node (ref "J2") (pin "A9") (pinfunction "A9_A9") (pintype "bidirectional"))
      (node (ref "J3") (pin "A9") (pinfunction "A9_A9") (pintype "bidirectional"))
      (node (ref "J4") (pin "A9") (pinfunction "A9_A9") (pintype "bidirectional"))
      (node (ref "J5") (pin "A9") (pinfunction "A9_A9") (pintype "bidirectional"))
      (node (ref "J6") (pin "A9") (pinfunction "A9_A9") (pintype "bidirectional"))
      (node (ref "J7") (pin "A9") (pinfunction "A9_A9") (pintype "bidirectional"))
      (node (ref "J8") (pin "A9") (pinfunction "A9_A9") (pintype "bidirectional"))
      (node (ref "J9") (pin "A9") (pinfunction "A9_A9") (pintype "bidirectional"))
      (node (ref "RN1") (pin "8") (pinfunction "R7_8") (pintype "bidirectional"))
    )
    (net (code "37") (name "/D7") (class "Default")
      (node (ref "J1") (pin "A10") (pinfunction "A10_A10") (pintype "bidirectional"))
      (node (ref "J10") (pin "A10") (pinfunction "A10_A10") (pintype "bidirectional"))
      (node (ref "J2") (pin "A10") (pinfunction "A10_A10") (pintype "bidirectional"))
      (node (ref "J3") (pin "A10") (pinfunction "A10_A10") (pintype "bidirectional"))
      (node (ref "J4") (pin "A10") (pinfunction "A10_A10") (pintype "bidirectional"))
      (node (ref "J5") (pin "A10") (pinfunction "A10_A10") (pintype "bidirectional"))
      (node (ref "J6") (pin "A10") (pinfunction "A10_A10") (pintype "bidirectional"))
      (node (ref "J7") (pin "A10") (pinfunction "A10_A10") (pintype "bidirectional"))
      (node (ref "J8") (pin "A10") (pinfunction "A10_A10") (pintype "bidirectional"))
      (node (ref "J9") (pin "A10") (pinfunction "A10_A10") (pintype "bidirectional"))
      (node (ref "RN1") (pin "9") (pinfunction "R8_9") (pintype "bidirectional"))
    )
    (net (code "38") (name "/DLD0") (class "Default")
      (node (ref "J1") (pin "A16") (pinfunction "A16_A16") (pintype "bidirectional"))
      (node (ref "J10") (pin "A16") (pinfunction "A16_A16") (pintype "bidirectional"))
      (node (ref "J2") (pin "A16") (pinfunction "A16_A16") (pintype "bidirectional"))
      (node (ref "J3") (pin "A16") (pinfunction "A16_A16") (pintype "bidirectional"))
      (node (ref "J4") (pin "A16") (pinfunction "A16_A16") (pintype "bidirectional"))
      (node (ref "J5") (pin "A16") (pinfunction "A16_A16") (pintype "bidirectional"))
      (node (ref "J6") (pin "A16") (pinfunction "A16_A16") (pintype "bidirectional"))
      (node (ref "J7") (pin "A16") (pinfunction "A16_A16") (pintype "bidirectional"))
      (node (ref "J8") (pin "A16") (pinfunction "A16_A16") (pintype "bidirectional"))
      (node (ref "J9") (pin "A16") (pinfunction "A16_A16") (pintype "bidirectional"))
    )
    (net (code "39") (name "/DLD1") (class "Default")
      (node (ref "J1") (pin "A17") (pinfunction "A17_A17") (pintype "bidirectional"))
      (node (ref "J10") (pin "A17") (pinfunction "A17_A17") (pintype "bidirectional"))
      (node (ref "J2") (pin "A17") (pinfunction "A17_A17") (pintype "bidirectional"))
      (node (ref "J3") (pin "A17") (pinfunction "A17_A17") (pintype "bidirectional"))
      (node (ref "J4") (pin "A17") (pinfunction "A17_A17") (pintype "bidirectional"))
      (node (ref "J5") (pin "A17") (pinfunction "A17_A17") (pintype "bidirectional"))
      (node (ref "J6") (pin "A17") (pinfunction "A17_A17") (pintype "bidirectional"))
      (node (ref "J7") (pin "A17") (pinfunction "A17_A17") (pintype "bidirectional"))
      (node (ref "J8") (pin "A17") (pinfunction "A17_A17") (pintype "bidirectional"))
      (node (ref "J9") (pin "A17") (pinfunction "A17_A17") (pintype "bidirectional"))
    )
    (net (code "40") (name "/DLD2") (class "Default")
      (node (ref "J1") (pin "A18") (pinfunction "A18_A18") (pintype "bidirectional"))
      (node (ref "J10") (pin "A18") (pinfunction "A18_A18") (pintype "bidirectional"))
      (node (ref "J2") (pin "A18") (pinfunction "A18_A18") (pintype "bidirectional"))
      (node (ref "J3") (pin "A18") (pinfunction "A18_A18") (pintype "bidirectional"))
      (node (ref "J4") (pin "A18") (pinfunction "A18_A18") (pintype "bidirectional"))
      (node (ref "J5") (pin "A18") (pinfunction "A18_A18") (pintype "bidirectional"))
      (node (ref "J6") (pin "A18") (pinfunction "A18_A18") (pintype "bidirectional"))
      (node (ref "J7") (pin "A18") (pinfunction "A18_A18") (pintype "bidirectional"))
      (node (ref "J8") (pin "A18") (pinfunction "A18_A18") (pintype "bidirectional"))
      (node (ref "J9") (pin "A18") (pinfunction "A18_A18") (pintype "bidirectional"))
    )
    (net (code "41") (name "/DLD3") (class "Default")
      (node (ref "J1") (pin "A19") (pinfunction "A19_A19") (pintype "bidirectional"))
      (node (ref "J10") (pin "A19") (pinfunction "A19_A19") (pintype "bidirectional"))
      (node (ref "J2") (pin "A19") (pinfunction "A19_A19") (pintype "bidirectional"))
      (node (ref "J3") (pin "A19") (pinfunction "A19_A19") (pintype "bidirectional"))
      (node (ref "J4") (pin "A19") (pinfunction "A19_A19") (pintype "bidirectional"))
      (node (ref "J5") (pin "A19") (pinfunction "A19_A19") (pintype "bidirectional"))
      (node (ref "J6") (pin "A19") (pinfunction "A19_A19") (pintype "bidirectional"))
      (node (ref "J7") (pin "A19") (pinfunction "A19_A19") (pintype "bidirectional"))
      (node (ref "J8") (pin "A19") (pinfunction "A19_A19") (pintype "bidirectional"))
      (node (ref "J9") (pin "A19") (pinfunction "A19_A19") (pintype "bidirectional"))
    )
    (net (code "42") (name "/DOE0") (class "Default")
      (node (ref "J1") (pin "A12") (pinfunction "A12_A12") (pintype "bidirectional"))
      (node (ref "J10") (pin "A12") (pinfunction "A12_A12") (pintype "bidirectional"))
      (node (ref "J2") (pin "A12") (pinfunction "A12_A12") (pintype "bidirectional"))
      (node (ref "J3") (pin "A12") (pinfunction "A12_A12") (pintype "bidirectional"))
      (node (ref "J4") (pin "A12") (pinfunction "A12_A12") (pintype "bidirectional"))
      (node (ref "J5") (pin "A12") (pinfunction "A12_A12") (pintype "bidirectional"))
      (node (ref "J6") (pin "A12") (pinfunction "A12_A12") (pintype "bidirectional"))
      (node (ref "J7") (pin "A12") (pinfunction "A12_A12") (pintype "bidirectional"))
      (node (ref "J8") (pin "A12") (pinfunction "A12_A12") (pintype "bidirectional"))
      (node (ref "J9") (pin "A12") (pinfunction "A12_A12") (pintype "bidirectional"))
    )
    (net (code "43") (name "/DOE1") (class "Default")
      (node (ref "J1") (pin "A13") (pinfunction "A13_A13") (pintype "bidirectional"))
      (node (ref "J10") (pin "A13") (pinfunction "A13_A13") (pintype "bidirectional"))
      (node (ref "J2") (pin "A13") (pinfunction "A13_A13") (pintype "bidirectional"))
      (node (ref "J3") (pin "A13") (pinfunction "A13_A13") (pintype "bidirectional"))
      (node (ref "J4") (pin "A13") (pinfunction "A13_A13") (pintype "bidirectional"))
      (node (ref "J5") (pin "A13") (pinfunction "A13_A13") (pintype "bidirectional"))
      (node (ref "J6") (pin "A13") (pinfunction "A13_A13") (pintype "bidirectional"))
      (node (ref "J7") (pin "A13") (pinfunction "A13_A13") (pintype "bidirectional"))
      (node (ref "J8") (pin "A13") (pinfunction "A13_A13") (pintype "bidirectional"))
      (node (ref "J9") (pin "A13") (pinfunction "A13_A13") (pintype "bidirectional"))
    )
    (net (code "44") (name "/DOE2") (class "Default")
      (node (ref "J1") (pin "A14") (pinfunction "A14_A14") (pintype "bidirectional"))
      (node (ref "J10") (pin "A14") (pinfunction "A14_A14") (pintype "bidirectional"))
      (node (ref "J2") (pin "A14") (pinfunction "A14_A14") (pintype "bidirectional"))
      (node (ref "J3") (pin "A14") (pinfunction "A14_A14") (pintype "bidirectional"))
      (node (ref "J4") (pin "A14") (pinfunction "A14_A14") (pintype "bidirectional"))
      (node (ref "J5") (pin "A14") (pinfunction "A14_A14") (pintype "bidirectional"))
      (node (ref "J6") (pin "A14") (pinfunction "A14_A14") (pintype "bidirectional"))
      (node (ref "J7") (pin "A14") (pinfunction "A14_A14") (pintype "bidirectional"))
      (node (ref "J8") (pin "A14") (pinfunction "A14_A14") (pintype "bidirectional"))
      (node (ref "J9") (pin "A14") (pinfunction "A14_A14") (pintype "bidirectional"))
    )
    (net (code "45") (name "/DOE3") (class "Default")
      (node (ref "J1") (pin "A15") (pinfunction "A15_A15") (pintype "bidirectional"))
      (node (ref "J10") (pin "A15") (pinfunction "A15_A15") (pintype "bidirectional"))
      (node (ref "J2") (pin "A15") (pinfunction "A15_A15") (pintype "bidirectional"))
      (node (ref "J3") (pin "A15") (pinfunction "A15_A15") (pintype "bidirectional"))
      (node (ref "J4") (pin "A15") (pinfunction "A15_A15") (pintype "bidirectional"))
      (node (ref "J5") (pin "A15") (pinfunction "A15_A15") (pintype "bidirectional"))
      (node (ref "J6") (pin "A15") (pinfunction "A15_A15") (pintype "bidirectional"))
      (node (ref "J7") (pin "A15") (pinfunction "A15_A15") (pintype "bidirectional"))
      (node (ref "J8") (pin "A15") (pinfunction "A15_A15") (pintype "bidirectional"))
      (node (ref "J9") (pin "A15") (pinfunction "A15_A15") (pintype "bidirectional"))
    )
    (net (code "46") (name "/FC") (class "Default")
      (node (ref "J1") (pin "A27") (pinfunction "A27_A27") (pintype "bidirectional"))
      (node (ref "J10") (pin "A27") (pinfunction "A27_A27") (pintype "bidirectional"))
      (node (ref "J2") (pin "A27") (pinfunction "A27_A27") (pintype "bidirectional"))
      (node (ref "J3") (pin "A27") (pinfunction "A27_A27") (pintype "bidirectional"))
      (node (ref "J4") (pin "A27") (pinfunction "A27_A27") (pintype "bidirectional"))
      (node (ref "J5") (pin "A27") (pinfunction "A27_A27") (pintype "bidirectional"))
      (node (ref "J6") (pin "A27") (pinfunction "A27_A27") (pintype "bidirectional"))
      (node (ref "J7") (pin "A27") (pinfunction "A27_A27") (pintype "bidirectional"))
      (node (ref "J8") (pin "A27") (pinfunction "A27_A27") (pintype "bidirectional"))
      (node (ref "J9") (pin "A27") (pinfunction "A27_A27") (pintype "bidirectional"))
    )
    (net (code "47") (name "/FN") (class "Default")
      (node (ref "J1") (pin "A29") (pinfunction "A29_A29") (pintype "bidirectional"))
      (node (ref "J10") (pin "A29") (pinfunction "A29_A29") (pintype "bidirectional"))
      (node (ref "J2") (pin "A29") (pinfunction "A29_A29") (pintype "bidirectional"))
      (node (ref "J3") (pin "A29") (pinfunction "A29_A29") (pintype "bidirectional"))
      (node (ref "J4") (pin "A29") (pinfunction "A29_A29") (pintype "bidirectional"))
      (node (ref "J5") (pin "A29") (pinfunction "A29_A29") (pintype "bidirectional"))
      (node (ref "J6") (pin "A29") (pinfunction "A29_A29") (pintype "bidirectional"))
      (node (ref "J7") (pin "A29") (pinfunction "A29_A29") (pintype "bidirectional"))
      (node (ref "J8") (pin "A29") (pinfunction "A29_A29") (pintype "bidirectional"))
      (node (ref "J9") (pin "A29") (pinfunction "A29_A29") (pintype "bidirectional"))
    )
    (net (code "48") (name "/FV") (class "Default")
      (node (ref "J1") (pin "A30") (pinfunction "A30_A30") (pintype "bidirectional"))
      (node (ref "J10") (pin "A30") (pinfunction "A30_A30") (pintype "bidirectional"))
      (node (ref "J2") (pin "A30") (pinfunction "A30_A30") (pintype "bidirectional"))
      (node (ref "J3") (pin "A30") (pinfunction "A30_A30") (pintype "bidirectional"))
      (node (ref "J4") (pin "A30") (pinfunction "A30_A30") (pintype "bidirectional"))
      (node (ref "J5") (pin "A30") (pinfunction "A30_A30") (pintype "bidirectional"))
      (node (ref "J6") (pin "A30") (pinfunction "A30_A30") (pintype "bidirectional"))
      (node (ref "J7") (pin "A30") (pinfunction "A30_A30") (pintype "bidirectional"))
      (node (ref "J8") (pin "A30") (pinfunction "A30_A30") (pintype "bidirectional"))
      (node (ref "J9") (pin "A30") (pinfunction "A30_A30") (pintype "bidirectional"))
    )
    (net (code "49") (name "/FZ") (class "Default")
      (node (ref "J1") (pin "A28") (pinfunction "A28_A28") (pintype "bidirectional"))
      (node (ref "J10") (pin "A28") (pinfunction "A28_A28") (pintype "bidirectional"))
      (node (ref "J2") (pin "A28") (pinfunction "A28_A28") (pintype "bidirectional"))
      (node (ref "J3") (pin "A28") (pinfunction "A28_A28") (pintype "bidirectional"))
      (node (ref "J4") (pin "A28") (pinfunction "A28_A28") (pintype "bidirectional"))
      (node (ref "J5") (pin "A28") (pinfunction "A28_A28") (pintype "bidirectional"))
      (node (ref "J6") (pin "A28") (pinfunction "A28_A28") (pintype "bidirectional"))
      (node (ref "J7") (pin "A28") (pinfunction "A28_A28") (pintype "bidirectional"))
      (node (ref "J8") (pin "A28") (pinfunction "A28_A28") (pintype "bidirectional"))
      (node (ref "J9") (pin "A28") (pinfunction "A28_A28") (pintype "bidirectional"))
    )
    (net (code "50") (name "/GND") (class "Default")
      (node (ref "C1") (pin "2") (pinfunction "2_2") (pintype "bidirectional"))
      (node (ref "C10") (pin "2") (pinfunction "2_2") (pintype "bidirectional"))
      (node (ref "C11") (pin "2") (pinfunction "-_2") (pintype "bidirectional"))
      (node (ref "C12") (pin "2") (pinfunction "-_2") (pintype "bidirectional"))
      (node (ref "C13") (pin "2") (pinfunction "2_2") (pintype "bidirectional"))
      (node (ref "C14") (pin "2") (pinfunction "2_2") (pintype "bidirectional"))
      (node (ref "C2") (pin "2") (pinfunction "2_2") (pintype "bidirectional"))
      (node (ref "C3") (pin "2") (pinfunction "2_2") (pintype "bidirectional"))
      (node (ref "C4") (pin "2") (pinfunction "2_2") (pintype "bidirectional"))
      (node (ref "C5") (pin "2") (pinfunction "2_2") (pintype "bidirectional"))
      (node (ref "C6") (pin "2") (pinfunction "2_2") (pintype "bidirectional"))
      (node (ref "C7") (pin "2") (pinfunction "2_2") (pintype "bidirectional"))
      (node (ref "C8") (pin "2") (pinfunction "2_2") (pintype "bidirectional"))
      (node (ref "C9") (pin "2") (pinfunction "2_2") (pintype "bidirectional"))
      (node (ref "J1") (pin "A31") (pinfunction "A31_A31") (pintype "bidirectional"))
      (node (ref "J1") (pin "A32") (pinfunction "A32_A32") (pintype "bidirectional"))
      (node (ref "J1") (pin "B11") (pinfunction "B11_B11") (pintype "bidirectional"))
      (node (ref "J1") (pin "B13") (pinfunction "B13_B13") (pintype "bidirectional"))
      (node (ref "J1") (pin "B15") (pinfunction "B15_B15") (pintype "bidirectional"))
      (node (ref "J1") (pin "B17") (pinfunction "B17_B17") (pintype "bidirectional"))
      (node (ref "J1") (pin "B19") (pinfunction "B19_B19") (pintype "bidirectional"))
      (node (ref "J1") (pin "B21") (pinfunction "B21_B21") (pintype "bidirectional"))
      (node (ref "J1") (pin "B23") (pinfunction "B23_B23") (pintype "bidirectional"))
      (node (ref "J1") (pin "B25") (pinfunction "B25_B25") (pintype "bidirectional"))
      (node (ref "J1") (pin "B3") (pinfunction "B3_B3") (pintype "bidirectional"))
      (node (ref "J1") (pin "B31") (pinfunction "B31_B31") (pintype "bidirectional"))
      (node (ref "J1") (pin "B32") (pinfunction "B32_B32") (pintype "bidirectional"))
      (node (ref "J1") (pin "B5") (pinfunction "B5_B5") (pintype "bidirectional"))
      (node (ref "J1") (pin "B7") (pinfunction "B7_B7") (pintype "bidirectional"))
      (node (ref "J1") (pin "B9") (pinfunction "B9_B9") (pintype "bidirectional"))
      (node (ref "J1") (pin "C31") (pinfunction "C31_C31") (pintype "bidirectional"))
      (node (ref "J1") (pin "C32") (pinfunction "C32_C32") (pintype "bidirectional"))
      (node (ref "J10") (pin "A31") (pinfunction "A31_A31") (pintype "bidirectional"))
      (node (ref "J10") (pin "A32") (pinfunction "A32_A32") (pintype "bidirectional"))
      (node (ref "J10") (pin "B11") (pinfunction "B11_B11") (pintype "bidirectional"))
      (node (ref "J10") (pin "B13") (pinfunction "B13_B13") (pintype "bidirectional"))
      (node (ref "J10") (pin "B15") (pinfunction "B15_B15") (pintype "bidirectional"))
      (node (ref "J10") (pin "B17") (pinfunction "B17_B17") (pintype "bidirectional"))
      (node (ref "J10") (pin "B19") (pinfunction "B19_B19") (pintype "bidirectional"))
      (node (ref "J10") (pin "B21") (pinfunction "B21_B21") (pintype "bidirectional"))
      (node (ref "J10") (pin "B23") (pinfunction "B23_B23") (pintype "bidirectional"))
      (node (ref "J10") (pin "B25") (pinfunction "B25_B25") (pintype "bidirectional"))
      (node (ref "J10") (pin "B3") (pinfunction "B3_B3") (pintype "bidirectional"))
      (node (ref "J10") (pin "B31") (pinfunction "B31_B31") (pintype "bidirectional"))
      (node (ref "J10") (pin "B32") (pinfunction "B32_B32") (pintype "bidirectional"))
      (node (ref "J10") (pin "B5") (pinfunction "B5_B5") (pintype "bidirectional"))
      (node (ref "J10") (pin "B7") (pinfunction "B7_B7") (pintype "bidirectional"))
      (node (ref "J10") (pin "B9") (pinfunction "B9_B9") (pintype "bidirectional"))
      (node (ref "J10") (pin "C31") (pinfunction "C31_C31") (pintype "bidirectional"))
      (node (ref "J10") (pin "C32") (pinfunction "C32_C32") (pintype "bidirectional"))
      (node (ref "J11") (pin "3") (pinfunction "3_3") (pintype "bidirectional"))
      (node (ref "J11") (pin "4") (pinfunction "4_4") (pintype "bidirectional"))
      (node (ref "J2") (pin "A31") (pinfunction "A31_A31") (pintype "bidirectional"))
      (node (ref "J2") (pin "A32") (pinfunction "A32_A32") (pintype "bidirectional"))
      (node (ref "J2") (pin "B11") (pinfunction "B11_B11") (pintype "bidirectional"))
      (node (ref "J2") (pin "B13") (pinfunction "B13_B13") (pintype "bidirectional"))
      (node (ref "J2") (pin "B15") (pinfunction "B15_B15") (pintype "bidirectional"))
      (node (ref "J2") (pin "B17") (pinfunction "B17_B17") (pintype "bidirectional"))
      (node (ref "J2") (pin "B19") (pinfunction "B19_B19") (pintype "bidirectional"))
      (node (ref "J2") (pin "B21") (pinfunction "B21_B21") (pintype "bidirectional"))
      (node (ref "J2") (pin "B23") (pinfunction "B23_B23") (pintype "bidirectional"))
      (node (ref "J2") (pin "B25") (pinfunction "B25_B25") (pintype "bidirectional"))
      (node (ref "J2") (pin "B3") (pinfunction "B3_B3") (pintype "bidirectional"))
      (node (ref "J2") (pin "B31") (pinfunction "B31_B31") (pintype "bidirectional"))
      (node (ref "J2") (pin "B32") (pinfunction "B32_B32") (pintype "bidirectional"))
      (node (ref "J2") (pin "B5") (pinfunction "B5_B5") (pintype "bidirectional"))
      (node (ref "J2") (pin "B7") (pinfunction "B7_B7") (pintype "bidirectional"))
      (node (ref "J2") (pin "B9") (pinfunction "B9_B9") (pintype "bidirectional"))
      (node (ref "J2") (pin "C31") (pinfunction "C31_C31") (pintype "bidirectional"))
      (node (ref "J2") (pin "C32") (pinfunction "C32_C32") (pintype "bidirectional"))
      (node (ref "J3") (pin "A31") (pinfunction "A31_A31") (pintype "bidirectional"))
      (node (ref "J3") (pin "A32") (pinfunction "A32_A32") (pintype "bidirectional"))
      (node (ref "J3") (pin "B11") (pinfunction "B11_B11") (pintype "bidirectional"))
      (node (ref "J3") (pin "B13") (pinfunction "B13_B13") (pintype "bidirectional"))
      (node (ref "J3") (pin "B15") (pinfunction "B15_B15") (pintype "bidirectional"))
      (node (ref "J3") (pin "B17") (pinfunction "B17_B17") (pintype "bidirectional"))
      (node (ref "J3") (pin "B19") (pinfunction "B19_B19") (pintype "bidirectional"))
      (node (ref "J3") (pin "B21") (pinfunction "B21_B21") (pintype "bidirectional"))
      (node (ref "J3") (pin "B23") (pinfunction "B23_B23") (pintype "bidirectional"))
      (node (ref "J3") (pin "B25") (pinfunction "B25_B25") (pintype "bidirectional"))
      (node (ref "J3") (pin "B3") (pinfunction "B3_B3") (pintype "bidirectional"))
      (node (ref "J3") (pin "B31") (pinfunction "B31_B31") (pintype "bidirectional"))
      (node (ref "J3") (pin "B32") (pinfunction "B32_B32") (pintype "bidirectional"))
      (node (ref "J3") (pin "B5") (pinfunction "B5_B5") (pintype "bidirectional"))
      (node (ref "J3") (pin "B7") (pinfunction "B7_B7") (pintype "bidirectional"))
      (node (ref "J3") (pin "B9") (pinfunction "B9_B9") (pintype "bidirectional"))
      (node (ref "J3") (pin "C31") (pinfunction "C31_C31") (pintype "bidirectional"))
      (node (ref "J3") (pin "C32") (pinfunction "C32_C32") (pintype "bidirectional"))
      (node (ref "J4") (pin "A31") (pinfunction "A31_A31") (pintype "bidirectional"))
      (node (ref "J4") (pin "A32") (pinfunction "A32_A32") (pintype "bidirectional"))
      (node (ref "J4") (pin "B11") (pinfunction "B11_B11") (pintype "bidirectional"))
      (node (ref "J4") (pin "B13") (pinfunction "B13_B13") (pintype "bidirectional"))
      (node (ref "J4") (pin "B15") (pinfunction "B15_B15") (pintype "bidirectional"))
      (node (ref "J4") (pin "B17") (pinfunction "B17_B17") (pintype "bidirectional"))
      (node (ref "J4") (pin "B19") (pinfunction "B19_B19") (pintype "bidirectional"))
      (node (ref "J4") (pin "B21") (pinfunction "B21_B21") (pintype "bidirectional"))
      (node (ref "J4") (pin "B23") (pinfunction "B23_B23") (pintype "bidirectional"))
      (node (ref "J4") (pin "B25") (pinfunction "B25_B25") (pintype "bidirectional"))
      (node (ref "J4") (pin "B3") (pinfunction "B3_B3") (pintype "bidirectional"))
      (node (ref "J4") (pin "B31") (pinfunction "B31_B31") (pintype "bidirectional"))
      (node (ref "J4") (pin "B32") (pinfunction "B32_B32") (pintype "bidirectional"))
      (node (ref "J4") (pin "B5") (pinfunction "B5_B5") (pintype "bidirectional"))
      (node (ref "J4") (pin "B7") (pinfunction "B7_B7") (pintype "bidirectional"))
      (node (ref "J4") (pin "B9") (pinfunction "B9_B9") (pintype "bidirectional"))
      (node (ref "J4") (pin "C31") (pinfunction "C31_C31") (pintype "bidirectional"))
      (node (ref "J4") (pin "C32") (pinfunction "C32_C32") (pintype "bidirectional"))
      (node (ref "J5") (pin "A31") (pinfunction "A31_A31") (pintype "bidirectional"))
      (node (ref "J5") (pin "A32") (pinfunction "A32_A32") (pintype "bidirectional"))
      (node (ref "J5") (pin "B11") (pinfunction "B11_B11") (pintype "bidirectional"))
      (node (ref "J5") (pin "B13") (pinfunction "B13_B13") (pintype "bidirectional"))
      (node (ref "J5") (pin "B15") (pinfunction "B15_B15") (pintype "bidirectional"))
      (node (ref "J5") (pin "B17") (pinfunction "B17_B17") (pintype "bidirectional"))
      (node (ref "J5") (pin "B19") (pinfunction "B19_B19") (pintype "bidirectional"))
      (node (ref "J5") (pin "B21") (pinfunction "B21_B21") (pintype "bidirectional"))
      (node (ref "J5") (pin "B23") (pinfunction "B23_B23") (pintype "bidirectional"))
      (node (ref "J5") (pin "B25") (pinfunction "B25_B25") (pintype "bidirectional"))
      (node (ref "J5") (pin "B3") (pinfunction "B3_B3") (pintype "bidirectional"))
      (node (ref "J5") (pin "B31") (pinfunction "B31_B31") (pintype "bidirectional"))
      (node (ref "J5") (pin "B32") (pinfunction "B32_B32") (pintype "bidirectional"))
      (node (ref "J5") (pin "B5") (pinfunction "B5_B5") (pintype "bidirectional"))
      (node (ref "J5") (pin "B7") (pinfunction "B7_B7") (pintype "bidirectional"))
      (node (ref "J5") (pin "B9") (pinfunction "B9_B9") (pintype "bidirectional"))
      (node (ref "J5") (pin "C31") (pinfunction "C31_C31") (pintype "bidirectional"))
      (node (ref "J5") (pin "C32") (pinfunction "C32_C32") (pintype "bidirectional"))
      (node (ref "J6") (pin "A31") (pinfunction "A31_A31") (pintype "bidirectional"))
      (node (ref "J6") (pin "A32") (pinfunction "A32_A32") (pintype "bidirectional"))
      (node (ref "J6") (pin "B11") (pinfunction "B11_B11") (pintype "bidirectional"))
      (node (ref "J6") (pin "B13") (pinfunction "B13_B13") (pintype "bidirectional"))
      (node (ref "J6") (pin "B15") (pinfunction "B15_B15") (pintype "bidirectional"))
      (node (ref "J6") (pin "B17") (pinfunction "B17_B17") (pintype "bidirectional"))
      (node (ref "J6") (pin "B19") (pinfunction "B19_B19") (pintype "bidirectional"))
      (node (ref "J6") (pin "B21") (pinfunction "B21_B21") (pintype "bidirectional"))
      (node (ref "J6") (pin "B23") (pinfunction "B23_B23") (pintype "bidirectional"))
      (node (ref "J6") (pin "B25") (pinfunction "B25_B25") (pintype "bidirectional"))
      (node (ref "J6") (pin "B3") (pinfunction "B3_B3") (pintype "bidirectional"))
      (node (ref "J6") (pin "B31") (pinfunction "B31_B31") (pintype "bidirectional"))
      (node (ref "J6") (pin "B32") (pinfunction "B32_B32") (pintype "bidirectional"))
      (node (ref "J6") (pin "B5") (pinfunction "B5_B5") (pintype "bidirectional"))
      (node (ref "J6") (pin "B7") (pinfunction "B7_B7") (pintype "bidirectional"))
      (node (ref "J6") (pin "B9") (pinfunction "B9_B9") (pintype "bidirectional"))
      (node (ref "J6") (pin "C31") (pinfunction "C31_C31") (pintype "bidirectional"))
      (node (ref "J6") (pin "C32") (pinfunction "C32_C32") (pintype "bidirectional"))
      (node (ref "J7") (pin "A31") (pinfunction "A31_A31") (pintype "bidirectional"))
      (node (ref "J7") (pin "A32") (pinfunction "A32_A32") (pintype "bidirectional"))
      (node (ref "J7") (pin "B11") (pinfunction "B11_B11") (pintype "bidirectional"))
      (node (ref "J7") (pin "B13") (pinfunction "B13_B13") (pintype "bidirectional"))
      (node (ref "J7") (pin "B15") (pinfunction "B15_B15") (pintype "bidirectional"))
      (node (ref "J7") (pin "B17") (pinfunction "B17_B17") (pintype "bidirectional"))
      (node (ref "J7") (pin "B19") (pinfunction "B19_B19") (pintype "bidirectional"))
      (node (ref "J7") (pin "B21") (pinfunction "B21_B21") (pintype "bidirectional"))
      (node (ref "J7") (pin "B23") (pinfunction "B23_B23") (pintype "bidirectional"))
      (node (ref "J7") (pin "B25") (pinfunction "B25_B25") (pintype "bidirectional"))
      (node (ref "J7") (pin "B3") (pinfunction "B3_B3") (pintype "bidirectional"))
      (node (ref "J7") (pin "B31") (pinfunction "B31_B31") (pintype "bidirectional"))
      (node (ref "J7") (pin "B32") (pinfunction "B32_B32") (pintype "bidirectional"))
      (node (ref "J7") (pin "B5") (pinfunction "B5_B5") (pintype "bidirectional"))
      (node (ref "J7") (pin "B7") (pinfunction "B7_B7") (pintype "bidirectional"))
      (node (ref "J7") (pin "B9") (pinfunction "B9_B9") (pintype "bidirectional"))
      (node (ref "J7") (pin "C31") (pinfunction "C31_C31") (pintype "bidirectional"))
      (node (ref "J7") (pin "C32") (pinfunction "C32_C32") (pintype "bidirectional"))
      (node (ref "J8") (pin "A31") (pinfunction "A31_A31") (pintype "bidirectional"))
      (node (ref "J8") (pin "A32") (pinfunction "A32_A32") (pintype "bidirectional"))
      (node (ref "J8") (pin "B11") (pinfunction "B11_B11") (pintype "bidirectional"))
      (node (ref "J8") (pin "B13") (pinfunction "B13_B13") (pintype "bidirectional"))
      (node (ref "J8") (pin "B15") (pinfunction "B15_B15") (pintype "bidirectional"))
      (node (ref "J8") (pin "B17") (pinfunction "B17_B17") (pintype "bidirectional"))
      (node (ref "J8") (pin "B19") (pinfunction "B19_B19") (pintype "bidirectional"))
      (node (ref "J8") (pin "B21") (pinfunction "B21_B21") (pintype "bidirectional"))
      (node (ref "J8") (pin "B23") (pinfunction "B23_B23") (pintype "bidirectional"))
      (node (ref "J8") (pin "B25") (pinfunction "B25_B25") (pintype "bidirectional"))
      (node (ref "J8") (pin "B3") (pinfunction "B3_B3") (pintype "bidirectional"))
      (node (ref "J8") (pin "B31") (pinfunction "B31_B31") (pintype "bidirectional"))
      (node (ref "J8") (pin "B32") (pinfunction "B32_B32") (pintype "bidirectional"))
      (node (ref "J8") (pin "B5") (pinfunction "B5_B5") (pintype "bidirectional"))
      (node (ref "J8") (pin "B7") (pinfunction "B7_B7") (pintype "bidirectional"))
      (node (ref "J8") (pin "B9") (pinfunction "B9_B9") (pintype "bidirectional"))
      (node (ref "J8") (pin "C31") (pinfunction "C31_C31") (pintype "bidirectional"))
      (node (ref "J8") (pin "C32") (pinfunction "C32_C32") (pintype "bidirectional"))
      (node (ref "J9") (pin "A31") (pinfunction "A31_A31") (pintype "bidirectional"))
      (node (ref "J9") (pin "A32") (pinfunction "A32_A32") (pintype "bidirectional"))
      (node (ref "J9") (pin "B11") (pinfunction "B11_B11") (pintype "bidirectional"))
      (node (ref "J9") (pin "B13") (pinfunction "B13_B13") (pintype "bidirectional"))
      (node (ref "J9") (pin "B15") (pinfunction "B15_B15") (pintype "bidirectional"))
      (node (ref "J9") (pin "B17") (pinfunction "B17_B17") (pintype "bidirectional"))
      (node (ref "J9") (pin "B19") (pinfunction "B19_B19") (pintype "bidirectional"))
      (node (ref "J9") (pin "B21") (pinfunction "B21_B21") (pintype "bidirectional"))
      (node (ref "J9") (pin "B23") (pinfunction "B23_B23") (pintype "bidirectional"))
      (node (ref "J9") (pin "B25") (pinfunction "B25_B25") (pintype "bidirectional"))
      (node (ref "J9") (pin "B3") (pinfunction "B3_B3") (pintype "bidirectional"))
      (node (ref "J9") (pin "B31") (pinfunction "B31_B31") (pintype "bidirectional"))
      (node (ref "J9") (pin "B32") (pinfunction "B32_B32") (pintype "bidirectional"))
      (node (ref "J9") (pin "B5") (pinfunction "B5_B5") (pintype "bidirectional"))
      (node (ref "J9") (pin "B7") (pinfunction "B7_B7") (pintype "bidirectional"))
      (node (ref "J9") (pin "B9") (pinfunction "B9_B9") (pintype "bidirectional"))
      (node (ref "J9") (pin "C31") (pinfunction "C31_C31") (pintype "bidirectional"))
      (node (ref "J9") (pin "C32") (pinfunction "C32_C32") (pintype "bidirectional"))
      (node (ref "LED1") (pin "1") (pinfunction "K_1") (pintype "bidirectional"))
    )
    (net (code "51") (name "/IRQ") (class "Default")
      (node (ref "J1") (pin "B29") (pinfunction "B29_B29") (pintype "bidirectional"))
      (node (ref "J10") (pin "B29") (pinfunction "B29_B29") (pintype "bidirectional"))
      (node (ref "J2") (pin "B29") (pinfunction "B29_B29") (pintype "bidirectional"))
      (node (ref "J3") (pin "B29") (pinfunction "B29_B29") (pintype "bidirectional"))
      (node (ref "J4") (pin "B29") (pinfunction "B29_B29") (pintype "bidirectional"))
      (node (ref "J5") (pin "B29") (pinfunction "B29_B29") (pintype "bidirectional"))
      (node (ref "J6") (pin "B29") (pinfunction "B29_B29") (pintype "bidirectional"))
      (node (ref "J7") (pin "B29") (pinfunction "B29_B29") (pintype "bidirectional"))
      (node (ref "J8") (pin "B29") (pinfunction "B29_B29") (pintype "bidirectional"))
      (node (ref "J9") (pin "B29") (pinfunction "B29_B29") (pintype "bidirectional"))
      (node (ref "R4") (pin "1") (pinfunction "1_1") (pintype "bidirectional"))
    )
    (net (code "52") (name "/LDF") (class "Default")
      (node (ref "J1") (pin "A26") (pinfunction "A26_A26") (pintype "bidirectional"))
      (node (ref "J10") (pin "A26") (pinfunction "A26_A26") (pintype "bidirectional"))
      (node (ref "J2") (pin "A26") (pinfunction "A26_A26") (pintype "bidirectional"))
      (node (ref "J3") (pin "A26") (pinfunction "A26_A26") (pintype "bidirectional"))
      (node (ref "J4") (pin "A26") (pinfunction "A26_A26") (pintype "bidirectional"))
      (node (ref "J5") (pin "A26") (pinfunction "A26_A26") (pintype "bidirectional"))
      (node (ref "J6") (pin "A26") (pinfunction "A26_A26") (pintype "bidirectional"))
      (node (ref "J7") (pin "A26") (pinfunction "A26_A26") (pintype "bidirectional"))
      (node (ref "J8") (pin "A26") (pinfunction "A26_A26") (pintype "bidirectional"))
      (node (ref "J9") (pin "A26") (pinfunction "A26_A26") (pintype "bidirectional"))
    )
    (net (code "53") (name "/LDZN") (class "Default")
      (node (ref "J1") (pin "C28") (pinfunction "C28_C28") (pintype "bidirectional"))
      (node (ref "J10") (pin "C28") (pinfunction "C28_C28") (pintype "bidirectional"))
      (node (ref "J2") (pin "C28") (pinfunction "C28_C28") (pintype "bidirectional"))
      (node (ref "J3") (pin "C28") (pinfunction "C28_C28") (pintype "bidirectional"))
      (node (ref "J4") (pin "C28") (pinfunction "C28_C28") (pintype "bidirectional"))
      (node (ref "J5") (pin "C28") (pinfunction "C28_C28") (pintype "bidirectional"))
      (node (ref "J6") (pin "C28") (pinfunction "C28_C28") (pintype "bidirectional"))
      (node (ref "J7") (pin "C28") (pinfunction "C28_C28") (pintype "bidirectional"))
      (node (ref "J8") (pin "C28") (pinfunction "C28_C28") (pintype "bidirectional"))
      (node (ref "J9") (pin "C28") (pinfunction "C28_C28") (pintype "bidirectional"))
    )
    (net (code "54") (name "/LED_A") (class "Default")
      (node (ref "LED1") (pin "2") (pinfunction "A_2") (pintype "bidirectional"))
      (node (ref "R1") (pin "2") (pinfunction "2_2") (pintype "bidirectional"))
    )
    (net (code "55") (name "/PDEC") (class "Default")
      (node (ref "J1") (pin "A23") (pinfunction "A23_A23") (pintype "bidirectional"))
      (node (ref "J10") (pin "A23") (pinfunction "A23_A23") (pintype "bidirectional"))
      (node (ref "J2") (pin "A23") (pinfunction "A23_A23") (pintype "bidirectional"))
      (node (ref "J3") (pin "A23") (pinfunction "A23_A23") (pintype "bidirectional"))
      (node (ref "J4") (pin "A23") (pinfunction "A23_A23") (pintype "bidirectional"))
      (node (ref "J5") (pin "A23") (pinfunction "A23_A23") (pintype "bidirectional"))
      (node (ref "J6") (pin "A23") (pinfunction "A23_A23") (pintype "bidirectional"))
      (node (ref "J7") (pin "A23") (pinfunction "A23_A23") (pintype "bidirectional"))
      (node (ref "J8") (pin "A23") (pinfunction "A23_A23") (pintype "bidirectional"))
      (node (ref "J9") (pin "A23") (pinfunction "A23_A23") (pintype "bidirectional"))
    )
    (net (code "56") (name "/PINC") (class "Default")
      (node (ref "J1") (pin "A22") (pinfunction "A22_A22") (pintype "bidirectional"))
      (node (ref "J10") (pin "A22") (pinfunction "A22_A22") (pintype "bidirectional"))
      (node (ref "J2") (pin "A22") (pinfunction "A22_A22") (pintype "bidirectional"))
      (node (ref "J3") (pin "A22") (pinfunction "A22_A22") (pintype "bidirectional"))
      (node (ref "J4") (pin "A22") (pinfunction "A22_A22") (pintype "bidirectional"))
      (node (ref "J5") (pin "A22") (pinfunction "A22_A22") (pintype "bidirectional"))
      (node (ref "J6") (pin "A22") (pinfunction "A22_A22") (pintype "bidirectional"))
      (node (ref "J7") (pin "A22") (pinfunction "A22_A22") (pintype "bidirectional"))
      (node (ref "J8") (pin "A22") (pinfunction "A22_A22") (pintype "bidirectional"))
      (node (ref "J9") (pin "A22") (pinfunction "A22_A22") (pintype "bidirectional"))
    )
    (net (code "57") (name "/PSEL0") (class "Default")
      (node (ref "J1") (pin "A20") (pinfunction "A20_A20") (pintype "bidirectional"))
      (node (ref "J10") (pin "A20") (pinfunction "A20_A20") (pintype "bidirectional"))
      (node (ref "J2") (pin "A20") (pinfunction "A20_A20") (pintype "bidirectional"))
      (node (ref "J3") (pin "A20") (pinfunction "A20_A20") (pintype "bidirectional"))
      (node (ref "J4") (pin "A20") (pinfunction "A20_A20") (pintype "bidirectional"))
      (node (ref "J5") (pin "A20") (pinfunction "A20_A20") (pintype "bidirectional"))
      (node (ref "J6") (pin "A20") (pinfunction "A20_A20") (pintype "bidirectional"))
      (node (ref "J7") (pin "A20") (pinfunction "A20_A20") (pintype "bidirectional"))
      (node (ref "J8") (pin "A20") (pinfunction "A20_A20") (pintype "bidirectional"))
      (node (ref "J9") (pin "A20") (pinfunction "A20_A20") (pintype "bidirectional"))
    )
    (net (code "58") (name "/PSEL1") (class "Default")
      (node (ref "J1") (pin "A21") (pinfunction "A21_A21") (pintype "bidirectional"))
      (node (ref "J10") (pin "A21") (pinfunction "A21_A21") (pintype "bidirectional"))
      (node (ref "J2") (pin "A21") (pinfunction "A21_A21") (pintype "bidirectional"))
      (node (ref "J3") (pin "A21") (pinfunction "A21_A21") (pintype "bidirectional"))
      (node (ref "J4") (pin "A21") (pinfunction "A21_A21") (pintype "bidirectional"))
      (node (ref "J5") (pin "A21") (pinfunction "A21_A21") (pintype "bidirectional"))
      (node (ref "J6") (pin "A21") (pinfunction "A21_A21") (pintype "bidirectional"))
      (node (ref "J7") (pin "A21") (pinfunction "A21_A21") (pintype "bidirectional"))
      (node (ref "J8") (pin "A21") (pinfunction "A21_A21") (pintype "bidirectional"))
      (node (ref "J9") (pin "A21") (pinfunction "A21_A21") (pintype "bidirectional"))
    )
    (net (code "59") (name "/PSEL2") (class "Default")
      (node (ref "J1") (pin "C27") (pinfunction "C27_C27") (pintype "bidirectional"))
      (node (ref "J10") (pin "C27") (pinfunction "C27_C27") (pintype "bidirectional"))
      (node (ref "J2") (pin "C27") (pinfunction "C27_C27") (pintype "bidirectional"))
      (node (ref "J3") (pin "C27") (pinfunction "C27_C27") (pintype "bidirectional"))
      (node (ref "J4") (pin "C27") (pinfunction "C27_C27") (pintype "bidirectional"))
      (node (ref "J5") (pin "C27") (pinfunction "C27_C27") (pintype "bidirectional"))
      (node (ref "J6") (pin "C27") (pinfunction "C27_C27") (pintype "bidirectional"))
      (node (ref "J7") (pin "C27") (pinfunction "C27_C27") (pintype "bidirectional"))
      (node (ref "J8") (pin "C27") (pinfunction "C27_C27") (pintype "bidirectional"))
      (node (ref "J9") (pin "C27") (pinfunction "C27_C27") (pintype "bidirectional"))
    )
    (net (code "60") (name "/SETC") (class "Default")
      (node (ref "J1") (pin "C30") (pinfunction "C30_C30") (pintype "bidirectional"))
      (node (ref "J10") (pin "C30") (pinfunction "C30_C30") (pintype "bidirectional"))
      (node (ref "J2") (pin "C30") (pinfunction "C30_C30") (pintype "bidirectional"))
      (node (ref "J3") (pin "C30") (pinfunction "C30_C30") (pintype "bidirectional"))
      (node (ref "J4") (pin "C30") (pinfunction "C30_C30") (pintype "bidirectional"))
      (node (ref "J5") (pin "C30") (pinfunction "C30_C30") (pintype "bidirectional"))
      (node (ref "J6") (pin "C30") (pinfunction "C30_C30") (pintype "bidirectional"))
      (node (ref "J7") (pin "C30") (pinfunction "C30_C30") (pintype "bidirectional"))
      (node (ref "J8") (pin "C30") (pinfunction "C30_C30") (pintype "bidirectional"))
      (node (ref "J9") (pin "C30") (pinfunction "C30_C30") (pintype "bidirectional"))
    )
    (net (code "61") (name "/SH0") (class "Default")
      (node (ref "J1") (pin "C25") (pinfunction "C25_C25") (pintype "bidirectional"))
      (node (ref "J10") (pin "C25") (pinfunction "C25_C25") (pintype "bidirectional"))
      (node (ref "J2") (pin "C25") (pinfunction "C25_C25") (pintype "bidirectional"))
      (node (ref "J3") (pin "C25") (pinfunction "C25_C25") (pintype "bidirectional"))
      (node (ref "J4") (pin "C25") (pinfunction "C25_C25") (pintype "bidirectional"))
      (node (ref "J5") (pin "C25") (pinfunction "C25_C25") (pintype "bidirectional"))
      (node (ref "J6") (pin "C25") (pinfunction "C25_C25") (pintype "bidirectional"))
      (node (ref "J7") (pin "C25") (pinfunction "C25_C25") (pintype "bidirectional"))
      (node (ref "J8") (pin "C25") (pinfunction "C25_C25") (pintype "bidirectional"))
      (node (ref "J9") (pin "C25") (pinfunction "C25_C25") (pintype "bidirectional"))
    )
    (net (code "62") (name "/SH1") (class "Default")
      (node (ref "J1") (pin "C26") (pinfunction "C26_C26") (pintype "bidirectional"))
      (node (ref "J10") (pin "C26") (pinfunction "C26_C26") (pintype "bidirectional"))
      (node (ref "J2") (pin "C26") (pinfunction "C26_C26") (pintype "bidirectional"))
      (node (ref "J3") (pin "C26") (pinfunction "C26_C26") (pintype "bidirectional"))
      (node (ref "J4") (pin "C26") (pinfunction "C26_C26") (pintype "bidirectional"))
      (node (ref "J5") (pin "C26") (pinfunction "C26_C26") (pintype "bidirectional"))
      (node (ref "J6") (pin "C26") (pinfunction "C26_C26") (pintype "bidirectional"))
      (node (ref "J7") (pin "C26") (pinfunction "C26_C26") (pintype "bidirectional"))
      (node (ref "J8") (pin "C26") (pinfunction "C26_C26") (pintype "bidirectional"))
      (node (ref "J9") (pin "C26") (pinfunction "C26_C26") (pintype "bidirectional"))
    )
    (net (code "63") (name "/SHCIN") (class "Default")
      (node (ref "J1") (pin "C29") (pinfunction "C29_C29") (pintype "bidirectional"))
      (node (ref "J10") (pin "C29") (pinfunction "C29_C29") (pintype "bidirectional"))
      (node (ref "J2") (pin "C29") (pinfunction "C29_C29") (pintype "bidirectional"))
      (node (ref "J3") (pin "C29") (pinfunction "C29_C29") (pintype "bidirectional"))
      (node (ref "J4") (pin "C29") (pinfunction "C29_C29") (pintype "bidirectional"))
      (node (ref "J5") (pin "C29") (pinfunction "C29_C29") (pintype "bidirectional"))
      (node (ref "J6") (pin "C29") (pinfunction "C29_C29") (pintype "bidirectional"))
      (node (ref "J7") (pin "C29") (pinfunction "C29_C29") (pintype "bidirectional"))
      (node (ref "J8") (pin "C29") (pinfunction "C29_C29") (pintype "bidirectional"))
      (node (ref "J9") (pin "C29") (pinfunction "C29_C29") (pintype "bidirectional"))
    )
    (net (code "64") (name "/SPARE11") (class "Default")
      (node (ref "J1") (pin "B30") (pinfunction "B30_B30") (pintype "bidirectional"))
      (node (ref "J10") (pin "B30") (pinfunction "B30_B30") (pintype "bidirectional"))
      (node (ref "J2") (pin "B30") (pinfunction "B30_B30") (pintype "bidirectional"))
      (node (ref "J3") (pin "B30") (pinfunction "B30_B30") (pintype "bidirectional"))
      (node (ref "J4") (pin "B30") (pinfunction "B30_B30") (pintype "bidirectional"))
      (node (ref "J5") (pin "B30") (pinfunction "B30_B30") (pintype "bidirectional"))
      (node (ref "J6") (pin "B30") (pinfunction "B30_B30") (pintype "bidirectional"))
      (node (ref "J7") (pin "B30") (pinfunction "B30_B30") (pintype "bidirectional"))
      (node (ref "J8") (pin "B30") (pinfunction "B30_B30") (pintype "bidirectional"))
      (node (ref "J9") (pin "B30") (pinfunction "B30_B30") (pintype "bidirectional"))
    )
    (net (code "65") (name "/SPARE12") (class "Default")
      (node (ref "J1") (pin "B4") (pinfunction "B4_B4") (pintype "bidirectional"))
      (node (ref "J10") (pin "B4") (pinfunction "B4_B4") (pintype "bidirectional"))
      (node (ref "J2") (pin "B4") (pinfunction "B4_B4") (pintype "bidirectional"))
      (node (ref "J3") (pin "B4") (pinfunction "B4_B4") (pintype "bidirectional"))
      (node (ref "J4") (pin "B4") (pinfunction "B4_B4") (pintype "bidirectional"))
      (node (ref "J5") (pin "B4") (pinfunction "B4_B4") (pintype "bidirectional"))
      (node (ref "J6") (pin "B4") (pinfunction "B4_B4") (pintype "bidirectional"))
      (node (ref "J7") (pin "B4") (pinfunction "B4_B4") (pintype "bidirectional"))
      (node (ref "J8") (pin "B4") (pinfunction "B4_B4") (pintype "bidirectional"))
      (node (ref "J9") (pin "B4") (pinfunction "B4_B4") (pintype "bidirectional"))
    )
    (net (code "66") (name "/SPARE13") (class "Default")
      (node (ref "J1") (pin "B6") (pinfunction "B6_B6") (pintype "bidirectional"))
      (node (ref "J10") (pin "B6") (pinfunction "B6_B6") (pintype "bidirectional"))
      (node (ref "J2") (pin "B6") (pinfunction "B6_B6") (pintype "bidirectional"))
      (node (ref "J3") (pin "B6") (pinfunction "B6_B6") (pintype "bidirectional"))
      (node (ref "J4") (pin "B6") (pinfunction "B6_B6") (pintype "bidirectional"))
      (node (ref "J5") (pin "B6") (pinfunction "B6_B6") (pintype "bidirectional"))
      (node (ref "J6") (pin "B6") (pinfunction "B6_B6") (pintype "bidirectional"))
      (node (ref "J7") (pin "B6") (pinfunction "B6_B6") (pintype "bidirectional"))
      (node (ref "J8") (pin "B6") (pinfunction "B6_B6") (pintype "bidirectional"))
      (node (ref "J9") (pin "B6") (pinfunction "B6_B6") (pintype "bidirectional"))
    )
    (net (code "67") (name "/SPARE14") (class "Default")
      (node (ref "J1") (pin "B8") (pinfunction "B8_B8") (pintype "bidirectional"))
      (node (ref "J10") (pin "B8") (pinfunction "B8_B8") (pintype "bidirectional"))
      (node (ref "J2") (pin "B8") (pinfunction "B8_B8") (pintype "bidirectional"))
      (node (ref "J3") (pin "B8") (pinfunction "B8_B8") (pintype "bidirectional"))
      (node (ref "J4") (pin "B8") (pinfunction "B8_B8") (pintype "bidirectional"))
      (node (ref "J5") (pin "B8") (pinfunction "B8_B8") (pintype "bidirectional"))
      (node (ref "J6") (pin "B8") (pinfunction "B8_B8") (pintype "bidirectional"))
      (node (ref "J7") (pin "B8") (pinfunction "B8_B8") (pintype "bidirectional"))
      (node (ref "J8") (pin "B8") (pinfunction "B8_B8") (pintype "bidirectional"))
      (node (ref "J9") (pin "B8") (pinfunction "B8_B8") (pintype "bidirectional"))
    )
    (net (code "68") (name "/SPARE15") (class "Default")
      (node (ref "J1") (pin "B10") (pinfunction "B10_B10") (pintype "bidirectional"))
      (node (ref "J10") (pin "B10") (pinfunction "B10_B10") (pintype "bidirectional"))
      (node (ref "J2") (pin "B10") (pinfunction "B10_B10") (pintype "bidirectional"))
      (node (ref "J3") (pin "B10") (pinfunction "B10_B10") (pintype "bidirectional"))
      (node (ref "J4") (pin "B10") (pinfunction "B10_B10") (pintype "bidirectional"))
      (node (ref "J5") (pin "B10") (pinfunction "B10_B10") (pintype "bidirectional"))
      (node (ref "J6") (pin "B10") (pinfunction "B10_B10") (pintype "bidirectional"))
      (node (ref "J7") (pin "B10") (pinfunction "B10_B10") (pintype "bidirectional"))
      (node (ref "J8") (pin "B10") (pinfunction "B10_B10") (pintype "bidirectional"))
      (node (ref "J9") (pin "B10") (pinfunction "B10_B10") (pintype "bidirectional"))
    )
    (net (code "69") (name "/SPARE16") (class "Default")
      (node (ref "J1") (pin "B12") (pinfunction "B12_B12") (pintype "bidirectional"))
      (node (ref "J10") (pin "B12") (pinfunction "B12_B12") (pintype "bidirectional"))
      (node (ref "J2") (pin "B12") (pinfunction "B12_B12") (pintype "bidirectional"))
      (node (ref "J3") (pin "B12") (pinfunction "B12_B12") (pintype "bidirectional"))
      (node (ref "J4") (pin "B12") (pinfunction "B12_B12") (pintype "bidirectional"))
      (node (ref "J5") (pin "B12") (pinfunction "B12_B12") (pintype "bidirectional"))
      (node (ref "J6") (pin "B12") (pinfunction "B12_B12") (pintype "bidirectional"))
      (node (ref "J7") (pin "B12") (pinfunction "B12_B12") (pintype "bidirectional"))
      (node (ref "J8") (pin "B12") (pinfunction "B12_B12") (pintype "bidirectional"))
      (node (ref "J9") (pin "B12") (pinfunction "B12_B12") (pintype "bidirectional"))
    )
    (net (code "70") (name "/SPARE17") (class "Default")
      (node (ref "J1") (pin "B14") (pinfunction "B14_B14") (pintype "bidirectional"))
      (node (ref "J10") (pin "B14") (pinfunction "B14_B14") (pintype "bidirectional"))
      (node (ref "J2") (pin "B14") (pinfunction "B14_B14") (pintype "bidirectional"))
      (node (ref "J3") (pin "B14") (pinfunction "B14_B14") (pintype "bidirectional"))
      (node (ref "J4") (pin "B14") (pinfunction "B14_B14") (pintype "bidirectional"))
      (node (ref "J5") (pin "B14") (pinfunction "B14_B14") (pintype "bidirectional"))
      (node (ref "J6") (pin "B14") (pinfunction "B14_B14") (pintype "bidirectional"))
      (node (ref "J7") (pin "B14") (pinfunction "B14_B14") (pintype "bidirectional"))
      (node (ref "J8") (pin "B14") (pinfunction "B14_B14") (pintype "bidirectional"))
      (node (ref "J9") (pin "B14") (pinfunction "B14_B14") (pintype "bidirectional"))
    )
    (net (code "71") (name "/SPARE18") (class "Default")
      (node (ref "J1") (pin "B16") (pinfunction "B16_B16") (pintype "bidirectional"))
      (node (ref "J10") (pin "B16") (pinfunction "B16_B16") (pintype "bidirectional"))
      (node (ref "J2") (pin "B16") (pinfunction "B16_B16") (pintype "bidirectional"))
      (node (ref "J3") (pin "B16") (pinfunction "B16_B16") (pintype "bidirectional"))
      (node (ref "J4") (pin "B16") (pinfunction "B16_B16") (pintype "bidirectional"))
      (node (ref "J5") (pin "B16") (pinfunction "B16_B16") (pintype "bidirectional"))
      (node (ref "J6") (pin "B16") (pinfunction "B16_B16") (pintype "bidirectional"))
      (node (ref "J7") (pin "B16") (pinfunction "B16_B16") (pintype "bidirectional"))
      (node (ref "J8") (pin "B16") (pinfunction "B16_B16") (pintype "bidirectional"))
      (node (ref "J9") (pin "B16") (pinfunction "B16_B16") (pintype "bidirectional"))
    )
    (net (code "72") (name "/SPARE19") (class "Default")
      (node (ref "J1") (pin "B18") (pinfunction "B18_B18") (pintype "bidirectional"))
      (node (ref "J10") (pin "B18") (pinfunction "B18_B18") (pintype "bidirectional"))
      (node (ref "J2") (pin "B18") (pinfunction "B18_B18") (pintype "bidirectional"))
      (node (ref "J3") (pin "B18") (pinfunction "B18_B18") (pintype "bidirectional"))
      (node (ref "J4") (pin "B18") (pinfunction "B18_B18") (pintype "bidirectional"))
      (node (ref "J5") (pin "B18") (pinfunction "B18_B18") (pintype "bidirectional"))
      (node (ref "J6") (pin "B18") (pinfunction "B18_B18") (pintype "bidirectional"))
      (node (ref "J7") (pin "B18") (pinfunction "B18_B18") (pintype "bidirectional"))
      (node (ref "J8") (pin "B18") (pinfunction "B18_B18") (pintype "bidirectional"))
      (node (ref "J9") (pin "B18") (pinfunction "B18_B18") (pintype "bidirectional"))
    )
    (net (code "73") (name "/SPARE20") (class "Default")
      (node (ref "J1") (pin "B20") (pinfunction "B20_B20") (pintype "bidirectional"))
      (node (ref "J10") (pin "B20") (pinfunction "B20_B20") (pintype "bidirectional"))
      (node (ref "J2") (pin "B20") (pinfunction "B20_B20") (pintype "bidirectional"))
      (node (ref "J3") (pin "B20") (pinfunction "B20_B20") (pintype "bidirectional"))
      (node (ref "J4") (pin "B20") (pinfunction "B20_B20") (pintype "bidirectional"))
      (node (ref "J5") (pin "B20") (pinfunction "B20_B20") (pintype "bidirectional"))
      (node (ref "J6") (pin "B20") (pinfunction "B20_B20") (pintype "bidirectional"))
      (node (ref "J7") (pin "B20") (pinfunction "B20_B20") (pintype "bidirectional"))
      (node (ref "J8") (pin "B20") (pinfunction "B20_B20") (pintype "bidirectional"))
      (node (ref "J9") (pin "B20") (pinfunction "B20_B20") (pintype "bidirectional"))
    )
    (net (code "74") (name "/SPARE21") (class "Default")
      (node (ref "J1") (pin "B22") (pinfunction "B22_B22") (pintype "bidirectional"))
      (node (ref "J10") (pin "B22") (pinfunction "B22_B22") (pintype "bidirectional"))
      (node (ref "J2") (pin "B22") (pinfunction "B22_B22") (pintype "bidirectional"))
      (node (ref "J3") (pin "B22") (pinfunction "B22_B22") (pintype "bidirectional"))
      (node (ref "J4") (pin "B22") (pinfunction "B22_B22") (pintype "bidirectional"))
      (node (ref "J5") (pin "B22") (pinfunction "B22_B22") (pintype "bidirectional"))
      (node (ref "J6") (pin "B22") (pinfunction "B22_B22") (pintype "bidirectional"))
      (node (ref "J7") (pin "B22") (pinfunction "B22_B22") (pintype "bidirectional"))
      (node (ref "J8") (pin "B22") (pinfunction "B22_B22") (pintype "bidirectional"))
      (node (ref "J9") (pin "B22") (pinfunction "B22_B22") (pintype "bidirectional"))
    )
    (net (code "75") (name "/SPARE22") (class "Default")
      (node (ref "J1") (pin "B24") (pinfunction "B24_B24") (pintype "bidirectional"))
      (node (ref "J10") (pin "B24") (pinfunction "B24_B24") (pintype "bidirectional"))
      (node (ref "J2") (pin "B24") (pinfunction "B24_B24") (pintype "bidirectional"))
      (node (ref "J3") (pin "B24") (pinfunction "B24_B24") (pintype "bidirectional"))
      (node (ref "J4") (pin "B24") (pinfunction "B24_B24") (pintype "bidirectional"))
      (node (ref "J5") (pin "B24") (pinfunction "B24_B24") (pintype "bidirectional"))
      (node (ref "J6") (pin "B24") (pinfunction "B24_B24") (pintype "bidirectional"))
      (node (ref "J7") (pin "B24") (pinfunction "B24_B24") (pintype "bidirectional"))
      (node (ref "J8") (pin "B24") (pinfunction "B24_B24") (pintype "bidirectional"))
      (node (ref "J9") (pin "B24") (pinfunction "B24_B24") (pintype "bidirectional"))
    )
    (net (code "76") (name "/SPARE23") (class "Default")
      (node (ref "J1") (pin "B26") (pinfunction "B26_B26") (pintype "bidirectional"))
      (node (ref "J10") (pin "B26") (pinfunction "B26_B26") (pintype "bidirectional"))
      (node (ref "J2") (pin "B26") (pinfunction "B26_B26") (pintype "bidirectional"))
      (node (ref "J3") (pin "B26") (pinfunction "B26_B26") (pintype "bidirectional"))
      (node (ref "J4") (pin "B26") (pinfunction "B26_B26") (pintype "bidirectional"))
      (node (ref "J5") (pin "B26") (pinfunction "B26_B26") (pintype "bidirectional"))
      (node (ref "J6") (pin "B26") (pinfunction "B26_B26") (pintype "bidirectional"))
      (node (ref "J7") (pin "B26") (pinfunction "B26_B26") (pintype "bidirectional"))
      (node (ref "J8") (pin "B26") (pinfunction "B26_B26") (pintype "bidirectional"))
      (node (ref "J9") (pin "B26") (pinfunction "B26_B26") (pintype "bidirectional"))
    )
    (net (code "77") (name "/VCC") (class "Default")
      (node (ref "C1") (pin "1") (pinfunction "1_1") (pintype "bidirectional"))
      (node (ref "C10") (pin "1") (pinfunction "1_1") (pintype "bidirectional"))
      (node (ref "C11") (pin "1") (pinfunction "+_1") (pintype "bidirectional"))
      (node (ref "C12") (pin "1") (pinfunction "+_1") (pintype "bidirectional"))
      (node (ref "C2") (pin "1") (pinfunction "1_1") (pintype "bidirectional"))
      (node (ref "C3") (pin "1") (pinfunction "1_1") (pintype "bidirectional"))
      (node (ref "C4") (pin "1") (pinfunction "1_1") (pintype "bidirectional"))
      (node (ref "C5") (pin "1") (pinfunction "1_1") (pintype "bidirectional"))
      (node (ref "C6") (pin "1") (pinfunction "1_1") (pintype "bidirectional"))
      (node (ref "C7") (pin "1") (pinfunction "1_1") (pintype "bidirectional"))
      (node (ref "C8") (pin "1") (pinfunction "1_1") (pintype "bidirectional"))
      (node (ref "C9") (pin "1") (pinfunction "1_1") (pintype "bidirectional"))
      (node (ref "J1") (pin "A1") (pinfunction "A1_A1") (pintype "bidirectional"))
      (node (ref "J1") (pin "A2") (pinfunction "A2_A2") (pintype "bidirectional"))
      (node (ref "J1") (pin "B1") (pinfunction "B1_B1") (pintype "bidirectional"))
      (node (ref "J1") (pin "B2") (pinfunction "B2_B2") (pintype "bidirectional"))
      (node (ref "J1") (pin "C1") (pinfunction "C1_C1") (pintype "bidirectional"))
      (node (ref "J1") (pin "C2") (pinfunction "C2_C2") (pintype "bidirectional"))
      (node (ref "J10") (pin "A1") (pinfunction "A1_A1") (pintype "bidirectional"))
      (node (ref "J10") (pin "A2") (pinfunction "A2_A2") (pintype "bidirectional"))
      (node (ref "J10") (pin "B1") (pinfunction "B1_B1") (pintype "bidirectional"))
      (node (ref "J10") (pin "B2") (pinfunction "B2_B2") (pintype "bidirectional"))
      (node (ref "J10") (pin "C1") (pinfunction "C1_C1") (pintype "bidirectional"))
      (node (ref "J10") (pin "C2") (pinfunction "C2_C2") (pintype "bidirectional"))
      (node (ref "J11") (pin "1") (pinfunction "1_1") (pintype "bidirectional"))
      (node (ref "J11") (pin "2") (pinfunction "2_2") (pintype "bidirectional"))
      (node (ref "J2") (pin "A1") (pinfunction "A1_A1") (pintype "bidirectional"))
      (node (ref "J2") (pin "A2") (pinfunction "A2_A2") (pintype "bidirectional"))
      (node (ref "J2") (pin "B1") (pinfunction "B1_B1") (pintype "bidirectional"))
      (node (ref "J2") (pin "B2") (pinfunction "B2_B2") (pintype "bidirectional"))
      (node (ref "J2") (pin "C1") (pinfunction "C1_C1") (pintype "bidirectional"))
      (node (ref "J2") (pin "C2") (pinfunction "C2_C2") (pintype "bidirectional"))
      (node (ref "J3") (pin "A1") (pinfunction "A1_A1") (pintype "bidirectional"))
      (node (ref "J3") (pin "A2") (pinfunction "A2_A2") (pintype "bidirectional"))
      (node (ref "J3") (pin "B1") (pinfunction "B1_B1") (pintype "bidirectional"))
      (node (ref "J3") (pin "B2") (pinfunction "B2_B2") (pintype "bidirectional"))
      (node (ref "J3") (pin "C1") (pinfunction "C1_C1") (pintype "bidirectional"))
      (node (ref "J3") (pin "C2") (pinfunction "C2_C2") (pintype "bidirectional"))
      (node (ref "J4") (pin "A1") (pinfunction "A1_A1") (pintype "bidirectional"))
      (node (ref "J4") (pin "A2") (pinfunction "A2_A2") (pintype "bidirectional"))
      (node (ref "J4") (pin "B1") (pinfunction "B1_B1") (pintype "bidirectional"))
      (node (ref "J4") (pin "B2") (pinfunction "B2_B2") (pintype "bidirectional"))
      (node (ref "J4") (pin "C1") (pinfunction "C1_C1") (pintype "bidirectional"))
      (node (ref "J4") (pin "C2") (pinfunction "C2_C2") (pintype "bidirectional"))
      (node (ref "J5") (pin "A1") (pinfunction "A1_A1") (pintype "bidirectional"))
      (node (ref "J5") (pin "A2") (pinfunction "A2_A2") (pintype "bidirectional"))
      (node (ref "J5") (pin "B1") (pinfunction "B1_B1") (pintype "bidirectional"))
      (node (ref "J5") (pin "B2") (pinfunction "B2_B2") (pintype "bidirectional"))
      (node (ref "J5") (pin "C1") (pinfunction "C1_C1") (pintype "bidirectional"))
      (node (ref "J5") (pin "C2") (pinfunction "C2_C2") (pintype "bidirectional"))
      (node (ref "J6") (pin "A1") (pinfunction "A1_A1") (pintype "bidirectional"))
      (node (ref "J6") (pin "A2") (pinfunction "A2_A2") (pintype "bidirectional"))
      (node (ref "J6") (pin "B1") (pinfunction "B1_B1") (pintype "bidirectional"))
      (node (ref "J6") (pin "B2") (pinfunction "B2_B2") (pintype "bidirectional"))
      (node (ref "J6") (pin "C1") (pinfunction "C1_C1") (pintype "bidirectional"))
      (node (ref "J6") (pin "C2") (pinfunction "C2_C2") (pintype "bidirectional"))
      (node (ref "J7") (pin "A1") (pinfunction "A1_A1") (pintype "bidirectional"))
      (node (ref "J7") (pin "A2") (pinfunction "A2_A2") (pintype "bidirectional"))
      (node (ref "J7") (pin "B1") (pinfunction "B1_B1") (pintype "bidirectional"))
      (node (ref "J7") (pin "B2") (pinfunction "B2_B2") (pintype "bidirectional"))
      (node (ref "J7") (pin "C1") (pinfunction "C1_C1") (pintype "bidirectional"))
      (node (ref "J7") (pin "C2") (pinfunction "C2_C2") (pintype "bidirectional"))
      (node (ref "J8") (pin "A1") (pinfunction "A1_A1") (pintype "bidirectional"))
      (node (ref "J8") (pin "A2") (pinfunction "A2_A2") (pintype "bidirectional"))
      (node (ref "J8") (pin "B1") (pinfunction "B1_B1") (pintype "bidirectional"))
      (node (ref "J8") (pin "B2") (pinfunction "B2_B2") (pintype "bidirectional"))
      (node (ref "J8") (pin "C1") (pinfunction "C1_C1") (pintype "bidirectional"))
      (node (ref "J8") (pin "C2") (pinfunction "C2_C2") (pintype "bidirectional"))
      (node (ref "J9") (pin "A1") (pinfunction "A1_A1") (pintype "bidirectional"))
      (node (ref "J9") (pin "A2") (pinfunction "A2_A2") (pintype "bidirectional"))
      (node (ref "J9") (pin "B1") (pinfunction "B1_B1") (pintype "bidirectional"))
      (node (ref "J9") (pin "B2") (pinfunction "B2_B2") (pintype "bidirectional"))
      (node (ref "J9") (pin "C1") (pinfunction "C1_C1") (pintype "bidirectional"))
      (node (ref "J9") (pin "C2") (pinfunction "C2_C2") (pintype "bidirectional"))
      (node (ref "R1") (pin "1") (pinfunction "1_1") (pintype "bidirectional"))
      (node (ref "R4") (pin "2") (pinfunction "2_2") (pintype "bidirectional"))
      (node (ref "RN1") (pin "1") (pinfunction "COM_1") (pintype "bidirectional"))
    )
  )
)
